# LEDs.net
KiCad netlist of a schematic drawn in Altium Designer
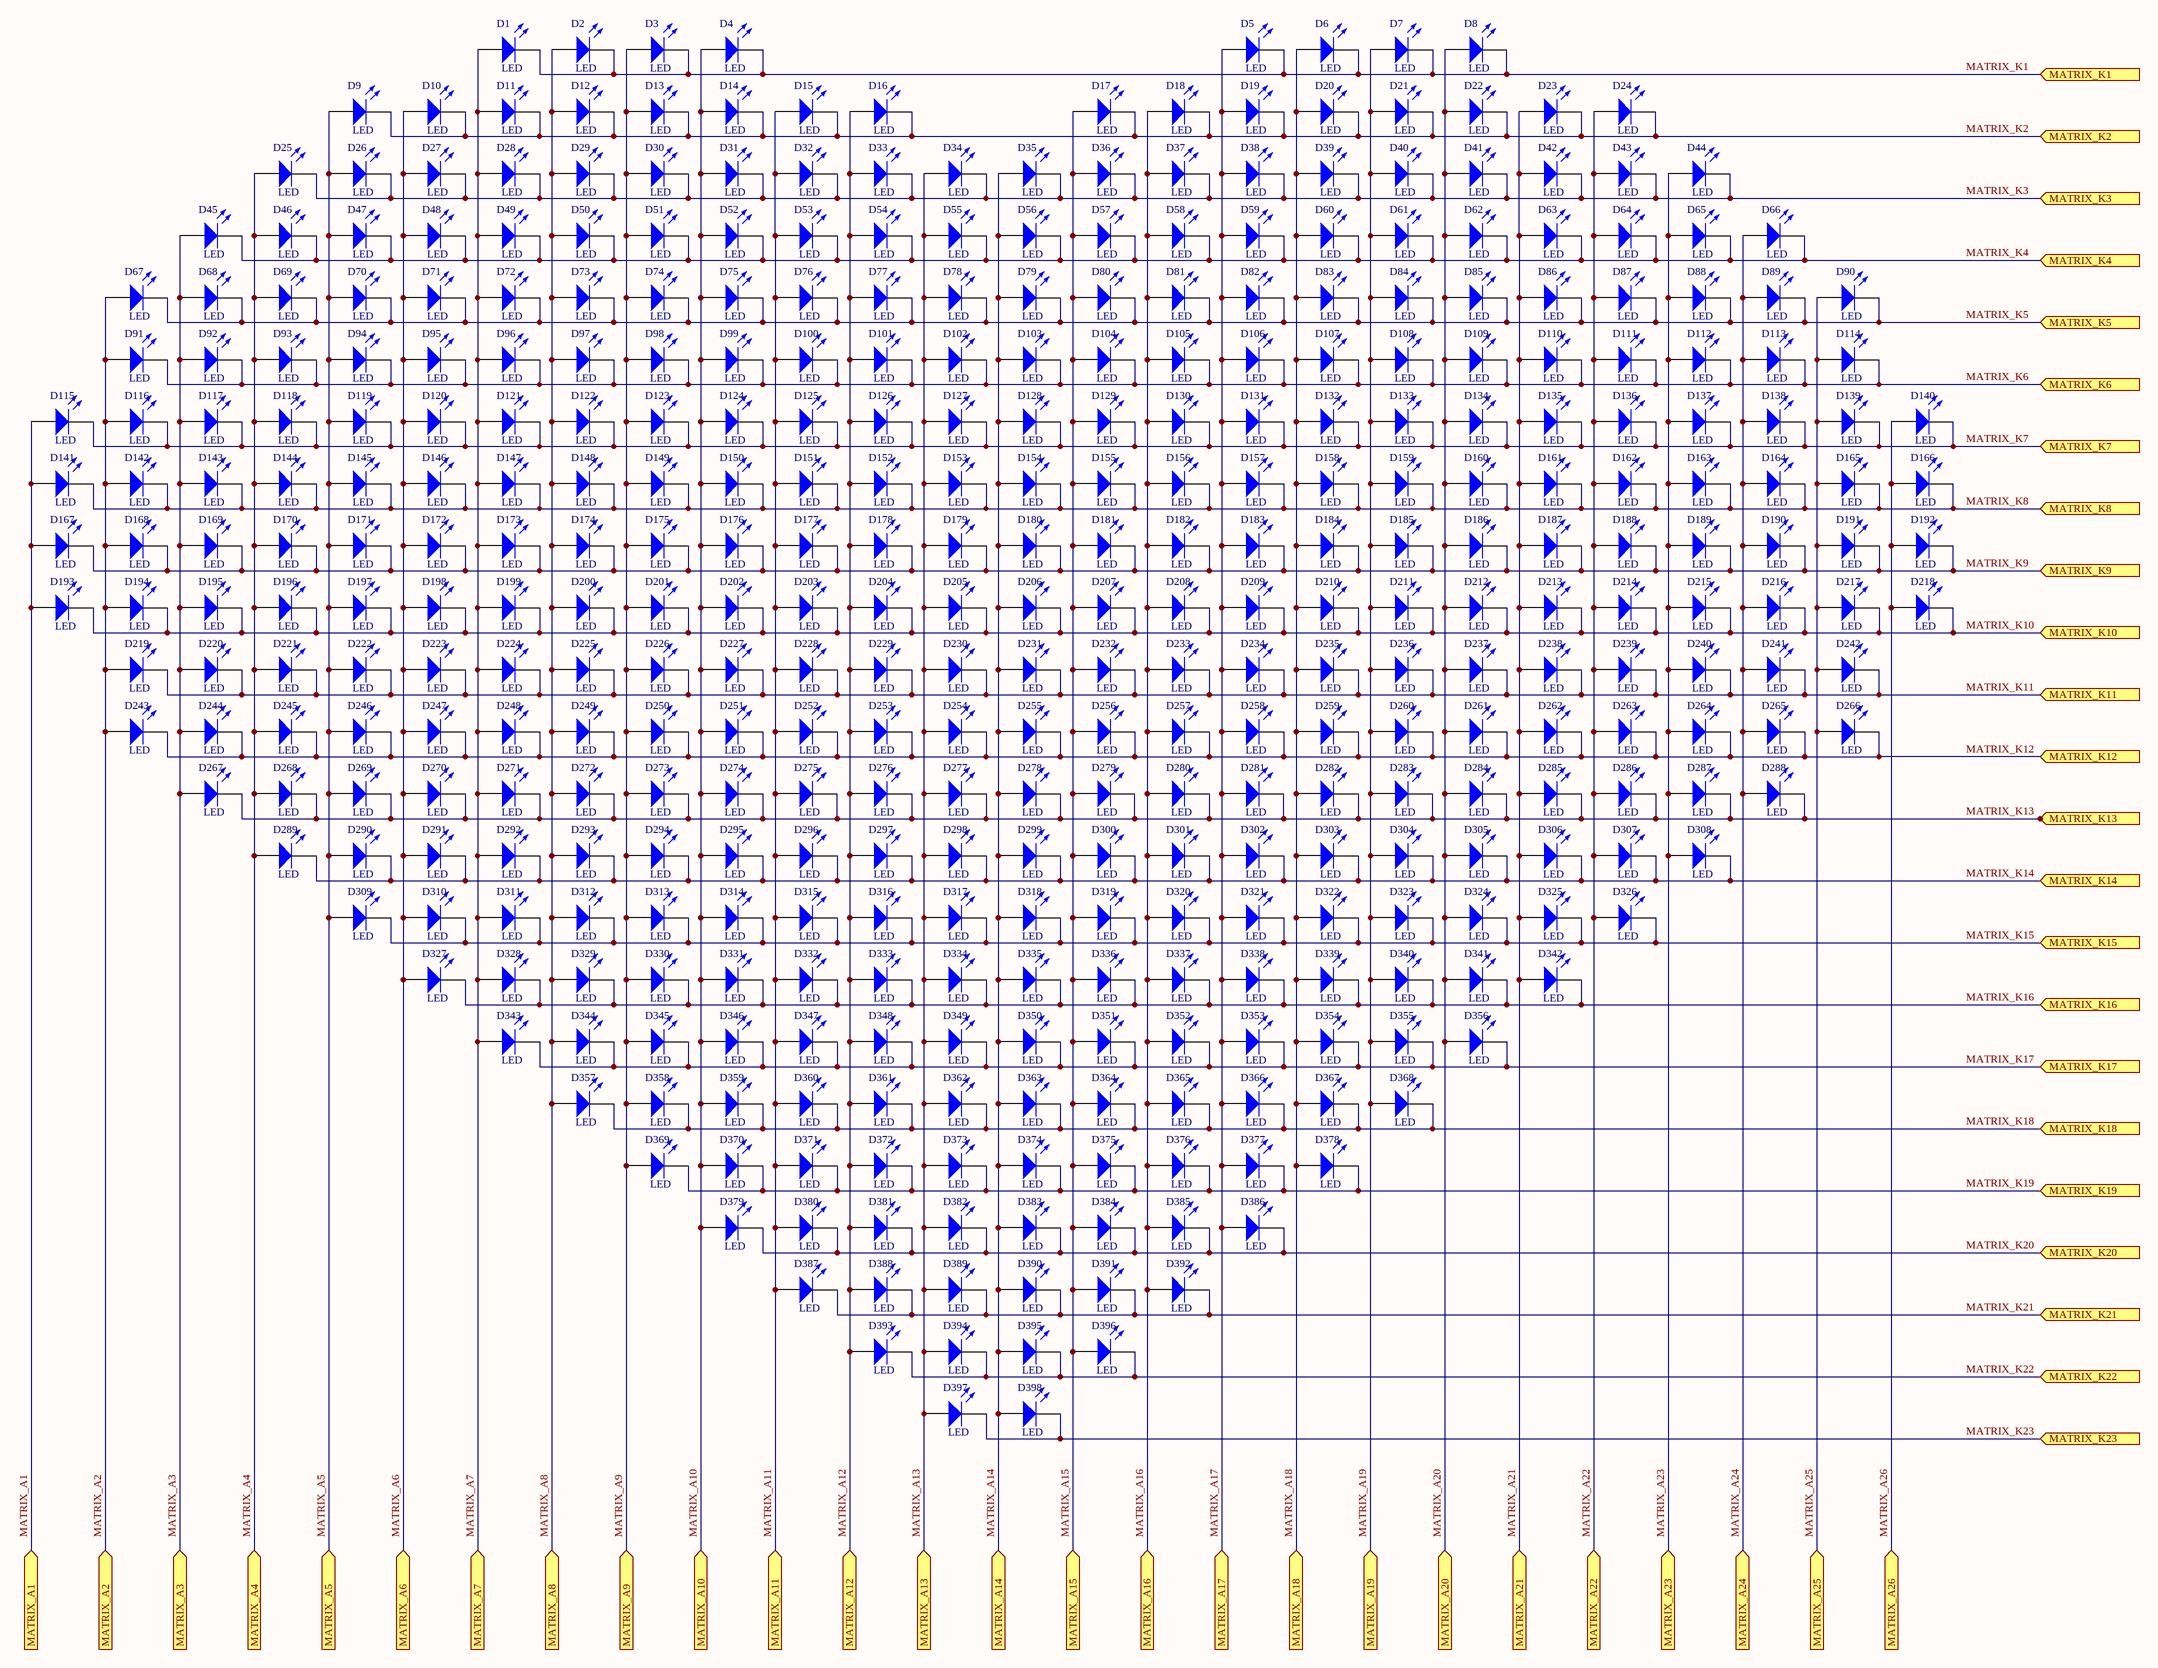
[diagram p0: LEDs.SchDoc]

(export (version "E")
  (design (tool "Eeschema 10.0.6"))
  (components
    (comp (ref "D1")
      (value "LED")
      (footprint "led_3mm")
      (description "Typical INFRARED GaAs LED")
      (fields (field (name "PUBLISHER") "Altium Limited"))
      (libsource (lib "Lib_Sch") (part "LED"))
    )
    (comp (ref "D2")
      (value "LED")
      (footprint "led_3mm")
      (description "Typical INFRARED GaAs LED")
      (fields (field (name "PUBLISHER") "Altium Limited"))
      (libsource (lib "Lib_Sch") (part "LED"))
    )
    (comp (ref "D3")
      (value "LED")
      (footprint "led_3mm")
      (description "Typical INFRARED GaAs LED")
      (fields (field (name "PUBLISHER") "Altium Limited"))
      (libsource (lib "Lib_Sch") (part "LED"))
    )
    (comp (ref "D4")
      (value "LED")
      (footprint "led_3mm")
      (description "Typical INFRARED GaAs LED")
      (fields (field (name "PUBLISHER") "Altium Limited"))
      (libsource (lib "Lib_Sch") (part "LED"))
    )
    (comp (ref "D5")
      (value "LED")
      (footprint "led_3mm")
      (description "Typical INFRARED GaAs LED")
      (fields (field (name "PUBLISHER") "Altium Limited"))
      (libsource (lib "Lib_Sch") (part "LED"))
    )
    (comp (ref "D6")
      (value "LED")
      (footprint "led_3mm")
      (description "Typical INFRARED GaAs LED")
      (fields (field (name "PUBLISHER") "Altium Limited"))
      (libsource (lib "Lib_Sch") (part "LED"))
    )
    (comp (ref "D7")
      (value "LED")
      (footprint "led_3mm")
      (description "Typical INFRARED GaAs LED")
      (fields (field (name "PUBLISHER") "Altium Limited"))
      (libsource (lib "Lib_Sch") (part "LED"))
    )
    (comp (ref "D8")
      (value "LED")
      (footprint "led_3mm")
      (description "Typical INFRARED GaAs LED")
      (fields (field (name "PUBLISHER") "Altium Limited"))
      (libsource (lib "Lib_Sch") (part "LED"))
    )
    (comp (ref "D9")
      (value "LED")
      (footprint "led_3mm")
      (description "Typical INFRARED GaAs LED")
      (fields (field (name "PUBLISHER") "Altium Limited"))
      (libsource (lib "Lib_Sch") (part "LED"))
    )
    (comp (ref "D10")
      (value "LED")
      (footprint "led_3mm")
      (description "Typical INFRARED GaAs LED")
      (fields (field (name "PUBLISHER") "Altium Limited"))
      (libsource (lib "Lib_Sch") (part "LED"))
    )
    (comp (ref "D11")
      (value "LED")
      (footprint "led_3mm")
      (description "Typical INFRARED GaAs LED")
      (fields (field (name "PUBLISHER") "Altium Limited"))
      (libsource (lib "Lib_Sch") (part "LED"))
    )
    (comp (ref "D12")
      (value "LED")
      (footprint "led_3mm")
      (description "Typical INFRARED GaAs LED")
      (fields (field (name "PUBLISHER") "Altium Limited"))
      (libsource (lib "Lib_Sch") (part "LED"))
    )
    (comp (ref "D13")
      (value "LED")
      (footprint "led_3mm")
      (description "Typical INFRARED GaAs LED")
      (fields (field (name "PUBLISHER") "Altium Limited"))
      (libsource (lib "Lib_Sch") (part "LED"))
    )
    (comp (ref "D14")
      (value "LED")
      (footprint "led_3mm")
      (description "Typical INFRARED GaAs LED")
      (fields (field (name "PUBLISHER") "Altium Limited"))
      (libsource (lib "Lib_Sch") (part "LED"))
    )
    (comp (ref "D15")
      (value "LED")
      (footprint "led_3mm")
      (description "Typical INFRARED GaAs LED")
      (fields (field (name "PUBLISHER") "Altium Limited"))
      (libsource (lib "Lib_Sch") (part "LED"))
    )
    (comp (ref "D16")
      (value "LED")
      (footprint "led_3mm")
      (description "Typical INFRARED GaAs LED")
      (fields (field (name "PUBLISHER") "Altium Limited"))
      (libsource (lib "Lib_Sch") (part "LED"))
    )
    (comp (ref "D17")
      (value "LED")
      (footprint "led_3mm")
      (description "Typical INFRARED GaAs LED")
      (fields (field (name "PUBLISHER") "Altium Limited"))
      (libsource (lib "Lib_Sch") (part "LED"))
    )
    (comp (ref "D18")
      (value "LED")
      (footprint "led_3mm")
      (description "Typical INFRARED GaAs LED")
      (fields (field (name "PUBLISHER") "Altium Limited"))
      (libsource (lib "Lib_Sch") (part "LED"))
    )
    (comp (ref "D19")
      (value "LED")
      (footprint "led_3mm")
      (description "Typical INFRARED GaAs LED")
      (fields (field (name "PUBLISHER") "Altium Limited"))
      (libsource (lib "Lib_Sch") (part "LED"))
    )
    (comp (ref "D20")
      (value "LED")
      (footprint "led_3mm")
      (description "Typical INFRARED GaAs LED")
      (fields (field (name "PUBLISHER") "Altium Limited"))
      (libsource (lib "Lib_Sch") (part "LED"))
    )
    (comp (ref "D21")
      (value "LED")
      (footprint "led_3mm")
      (description "Typical INFRARED GaAs LED")
      (fields (field (name "PUBLISHER") "Altium Limited"))
      (libsource (lib "Lib_Sch") (part "LED"))
    )
    (comp (ref "D22")
      (value "LED")
      (footprint "led_3mm")
      (description "Typical INFRARED GaAs LED")
      (fields (field (name "PUBLISHER") "Altium Limited"))
      (libsource (lib "Lib_Sch") (part "LED"))
    )
    (comp (ref "D23")
      (value "LED")
      (footprint "led_3mm")
      (description "Typical INFRARED GaAs LED")
      (fields (field (name "PUBLISHER") "Altium Limited"))
      (libsource (lib "Lib_Sch") (part "LED"))
    )
    (comp (ref "D24")
      (value "LED")
      (footprint "led_3mm")
      (description "Typical INFRARED GaAs LED")
      (fields (field (name "PUBLISHER") "Altium Limited"))
      (libsource (lib "Lib_Sch") (part "LED"))
    )
    (comp (ref "D25")
      (value "LED")
      (footprint "led_3mm")
      (description "Typical INFRARED GaAs LED")
      (fields (field (name "PUBLISHER") "Altium Limited"))
      (libsource (lib "Lib_Sch") (part "LED"))
    )
    (comp (ref "D26")
      (value "LED")
      (footprint "led_3mm")
      (description "Typical INFRARED GaAs LED")
      (fields (field (name "PUBLISHER") "Altium Limited"))
      (libsource (lib "Lib_Sch") (part "LED"))
    )
    (comp (ref "D27")
      (value "LED")
      (footprint "led_3mm")
      (description "Typical INFRARED GaAs LED")
      (fields (field (name "PUBLISHER") "Altium Limited"))
      (libsource (lib "Lib_Sch") (part "LED"))
    )
    (comp (ref "D28")
      (value "LED")
      (footprint "led_3mm")
      (description "Typical INFRARED GaAs LED")
      (fields (field (name "PUBLISHER") "Altium Limited"))
      (libsource (lib "Lib_Sch") (part "LED"))
    )
    (comp (ref "D29")
      (value "LED")
      (footprint "led_3mm")
      (description "Typical INFRARED GaAs LED")
      (fields (field (name "PUBLISHER") "Altium Limited"))
      (libsource (lib "Lib_Sch") (part "LED"))
    )
    (comp (ref "D30")
      (value "LED")
      (footprint "led_3mm")
      (description "Typical INFRARED GaAs LED")
      (fields (field (name "PUBLISHER") "Altium Limited"))
      (libsource (lib "Lib_Sch") (part "LED"))
    )
    (comp (ref "D31")
      (value "LED")
      (footprint "led_3mm")
      (description "Typical INFRARED GaAs LED")
      (fields (field (name "PUBLISHER") "Altium Limited"))
      (libsource (lib "Lib_Sch") (part "LED"))
    )
    (comp (ref "D32")
      (value "LED")
      (footprint "led_3mm")
      (description "Typical INFRARED GaAs LED")
      (fields (field (name "PUBLISHER") "Altium Limited"))
      (libsource (lib "Lib_Sch") (part "LED"))
    )
    (comp (ref "D33")
      (value "LED")
      (footprint "led_3mm")
      (description "Typical INFRARED GaAs LED")
      (fields (field (name "PUBLISHER") "Altium Limited"))
      (libsource (lib "Lib_Sch") (part "LED"))
    )
    (comp (ref "D34")
      (value "LED")
      (footprint "led_3mm")
      (description "Typical INFRARED GaAs LED")
      (fields (field (name "PUBLISHER") "Altium Limited"))
      (libsource (lib "Lib_Sch") (part "LED"))
    )
    (comp (ref "D35")
      (value "LED")
      (footprint "led_3mm")
      (description "Typical INFRARED GaAs LED")
      (fields (field (name "PUBLISHER") "Altium Limited"))
      (libsource (lib "Lib_Sch") (part "LED"))
    )
    (comp (ref "D36")
      (value "LED")
      (footprint "led_3mm")
      (description "Typical INFRARED GaAs LED")
      (fields (field (name "PUBLISHER") "Altium Limited"))
      (libsource (lib "Lib_Sch") (part "LED"))
    )
    (comp (ref "D37")
      (value "LED")
      (footprint "led_3mm")
      (description "Typical INFRARED GaAs LED")
      (fields (field (name "PUBLISHER") "Altium Limited"))
      (libsource (lib "Lib_Sch") (part "LED"))
    )
    (comp (ref "D38")
      (value "LED")
      (footprint "led_3mm")
      (description "Typical INFRARED GaAs LED")
      (fields (field (name "PUBLISHER") "Altium Limited"))
      (libsource (lib "Lib_Sch") (part "LED"))
    )
    (comp (ref "D39")
      (value "LED")
      (footprint "led_3mm")
      (description "Typical INFRARED GaAs LED")
      (fields (field (name "PUBLISHER") "Altium Limited"))
      (libsource (lib "Lib_Sch") (part "LED"))
    )
    (comp (ref "D40")
      (value "LED")
      (footprint "led_3mm")
      (description "Typical INFRARED GaAs LED")
      (fields (field (name "PUBLISHER") "Altium Limited"))
      (libsource (lib "Lib_Sch") (part "LED"))
    )
    (comp (ref "D41")
      (value "LED")
      (footprint "led_3mm")
      (description "Typical INFRARED GaAs LED")
      (fields (field (name "PUBLISHER") "Altium Limited"))
      (libsource (lib "Lib_Sch") (part "LED"))
    )
    (comp (ref "D42")
      (value "LED")
      (footprint "led_3mm")
      (description "Typical INFRARED GaAs LED")
      (fields (field (name "PUBLISHER") "Altium Limited"))
      (libsource (lib "Lib_Sch") (part "LED"))
    )
    (comp (ref "D43")
      (value "LED")
      (footprint "led_3mm")
      (description "Typical INFRARED GaAs LED")
      (fields (field (name "PUBLISHER") "Altium Limited"))
      (libsource (lib "Lib_Sch") (part "LED"))
    )
    (comp (ref "D44")
      (value "LED")
      (footprint "led_3mm")
      (description "Typical INFRARED GaAs LED")
      (fields (field (name "PUBLISHER") "Altium Limited"))
      (libsource (lib "Lib_Sch") (part "LED"))
    )
    (comp (ref "D45")
      (value "LED")
      (footprint "led_3mm")
      (description "Typical INFRARED GaAs LED")
      (fields (field (name "PUBLISHER") "Altium Limited"))
      (libsource (lib "Lib_Sch") (part "LED"))
    )
    (comp (ref "D46")
      (value "LED")
      (footprint "led_3mm")
      (description "Typical INFRARED GaAs LED")
      (fields (field (name "PUBLISHER") "Altium Limited"))
      (libsource (lib "Lib_Sch") (part "LED"))
    )
    (comp (ref "D47")
      (value "LED")
      (footprint "led_3mm")
      (description "Typical INFRARED GaAs LED")
      (fields (field (name "PUBLISHER") "Altium Limited"))
      (libsource (lib "Lib_Sch") (part "LED"))
    )
    (comp (ref "D48")
      (value "LED")
      (footprint "led_3mm")
      (description "Typical INFRARED GaAs LED")
      (fields (field (name "PUBLISHER") "Altium Limited"))
      (libsource (lib "Lib_Sch") (part "LED"))
    )
    (comp (ref "D49")
      (value "LED")
      (footprint "led_3mm")
      (description "Typical INFRARED GaAs LED")
      (fields (field (name "PUBLISHER") "Altium Limited"))
      (libsource (lib "Lib_Sch") (part "LED"))
    )
    (comp (ref "D50")
      (value "LED")
      (footprint "led_3mm")
      (description "Typical INFRARED GaAs LED")
      (fields (field (name "PUBLISHER") "Altium Limited"))
      (libsource (lib "Lib_Sch") (part "LED"))
    )
    (comp (ref "D51")
      (value "LED")
      (footprint "led_3mm")
      (description "Typical INFRARED GaAs LED")
      (fields (field (name "PUBLISHER") "Altium Limited"))
      (libsource (lib "Lib_Sch") (part "LED"))
    )
    (comp (ref "D52")
      (value "LED")
      (footprint "led_3mm")
      (description "Typical INFRARED GaAs LED")
      (fields (field (name "PUBLISHER") "Altium Limited"))
      (libsource (lib "Lib_Sch") (part "LED"))
    )
    (comp (ref "D53")
      (value "LED")
      (footprint "led_3mm")
      (description "Typical INFRARED GaAs LED")
      (fields (field (name "PUBLISHER") "Altium Limited"))
      (libsource (lib "Lib_Sch") (part "LED"))
    )
    (comp (ref "D54")
      (value "LED")
      (footprint "led_3mm")
      (description "Typical INFRARED GaAs LED")
      (fields (field (name "PUBLISHER") "Altium Limited"))
      (libsource (lib "Lib_Sch") (part "LED"))
    )
    (comp (ref "D55")
      (value "LED")
      (footprint "led_3mm")
      (description "Typical INFRARED GaAs LED")
      (fields (field (name "PUBLISHER") "Altium Limited"))
      (libsource (lib "Lib_Sch") (part "LED"))
    )
    (comp (ref "D56")
      (value "LED")
      (footprint "led_3mm")
      (description "Typical INFRARED GaAs LED")
      (fields (field (name "PUBLISHER") "Altium Limited"))
      (libsource (lib "Lib_Sch") (part "LED"))
    )
    (comp (ref "D57")
      (value "LED")
      (footprint "led_3mm")
      (description "Typical INFRARED GaAs LED")
      (fields (field (name "PUBLISHER") "Altium Limited"))
      (libsource (lib "Lib_Sch") (part "LED"))
    )
    (comp (ref "D58")
      (value "LED")
      (footprint "led_3mm")
      (description "Typical INFRARED GaAs LED")
      (fields (field (name "PUBLISHER") "Altium Limited"))
      (libsource (lib "Lib_Sch") (part "LED"))
    )
    (comp (ref "D59")
      (value "LED")
      (footprint "led_3mm")
      (description "Typical INFRARED GaAs LED")
      (fields (field (name "PUBLISHER") "Altium Limited"))
      (libsource (lib "Lib_Sch") (part "LED"))
    )
    (comp (ref "D60")
      (value "LED")
      (footprint "led_3mm")
      (description "Typical INFRARED GaAs LED")
      (fields (field (name "PUBLISHER") "Altium Limited"))
      (libsource (lib "Lib_Sch") (part "LED"))
    )
    (comp (ref "D61")
      (value "LED")
      (footprint "led_3mm")
      (description "Typical INFRARED GaAs LED")
      (fields (field (name "PUBLISHER") "Altium Limited"))
      (libsource (lib "Lib_Sch") (part "LED"))
    )
    (comp (ref "D62")
      (value "LED")
      (footprint "led_3mm")
      (description "Typical INFRARED GaAs LED")
      (fields (field (name "PUBLISHER") "Altium Limited"))
      (libsource (lib "Lib_Sch") (part "LED"))
    )
    (comp (ref "D63")
      (value "LED")
      (footprint "led_3mm")
      (description "Typical INFRARED GaAs LED")
      (fields (field (name "PUBLISHER") "Altium Limited"))
      (libsource (lib "Lib_Sch") (part "LED"))
    )
    (comp (ref "D64")
      (value "LED")
      (footprint "led_3mm")
      (description "Typical INFRARED GaAs LED")
      (fields (field (name "PUBLISHER") "Altium Limited"))
      (libsource (lib "Lib_Sch") (part "LED"))
    )
    (comp (ref "D65")
      (value "LED")
      (footprint "led_3mm")
      (description "Typical INFRARED GaAs LED")
      (fields (field (name "PUBLISHER") "Altium Limited"))
      (libsource (lib "Lib_Sch") (part "LED"))
    )
    (comp (ref "D66")
      (value "LED")
      (footprint "led_3mm")
      (description "Typical INFRARED GaAs LED")
      (fields (field (name "PUBLISHER") "Altium Limited"))
      (libsource (lib "Lib_Sch") (part "LED"))
    )
    (comp (ref "D67")
      (value "LED")
      (footprint "led_3mm")
      (description "Typical INFRARED GaAs LED")
      (fields (field (name "PUBLISHER") "Altium Limited"))
      (libsource (lib "Lib_Sch") (part "LED"))
    )
    (comp (ref "D68")
      (value "LED")
      (footprint "led_3mm")
      (description "Typical INFRARED GaAs LED")
      (fields (field (name "PUBLISHER") "Altium Limited"))
      (libsource (lib "Lib_Sch") (part "LED"))
    )
    (comp (ref "D69")
      (value "LED")
      (footprint "led_3mm")
      (description "Typical INFRARED GaAs LED")
      (fields (field (name "PUBLISHER") "Altium Limited"))
      (libsource (lib "Lib_Sch") (part "LED"))
    )
    (comp (ref "D70")
      (value "LED")
      (footprint "led_3mm")
      (description "Typical INFRARED GaAs LED")
      (fields (field (name "PUBLISHER") "Altium Limited"))
      (libsource (lib "Lib_Sch") (part "LED"))
    )
    (comp (ref "D71")
      (value "LED")
      (footprint "led_3mm")
      (description "Typical INFRARED GaAs LED")
      (fields (field (name "PUBLISHER") "Altium Limited"))
      (libsource (lib "Lib_Sch") (part "LED"))
    )
    (comp (ref "D72")
      (value "LED")
      (footprint "led_3mm")
      (description "Typical INFRARED GaAs LED")
      (fields (field (name "PUBLISHER") "Altium Limited"))
      (libsource (lib "Lib_Sch") (part "LED"))
    )
    (comp (ref "D73")
      (value "LED")
      (footprint "led_3mm")
      (description "Typical INFRARED GaAs LED")
      (fields (field (name "PUBLISHER") "Altium Limited"))
      (libsource (lib "Lib_Sch") (part "LED"))
    )
    (comp (ref "D74")
      (value "LED")
      (footprint "led_3mm")
      (description "Typical INFRARED GaAs LED")
      (fields (field (name "PUBLISHER") "Altium Limited"))
      (libsource (lib "Lib_Sch") (part "LED"))
    )
    (comp (ref "D75")
      (value "LED")
      (footprint "led_3mm")
      (description "Typical INFRARED GaAs LED")
      (fields (field (name "PUBLISHER") "Altium Limited"))
      (libsource (lib "Lib_Sch") (part "LED"))
    )
    (comp (ref "D76")
      (value "LED")
      (footprint "led_3mm")
      (description "Typical INFRARED GaAs LED")
      (fields (field (name "PUBLISHER") "Altium Limited"))
      (libsource (lib "Lib_Sch") (part "LED"))
    )
    (comp (ref "D77")
      (value "LED")
      (footprint "led_3mm")
      (description "Typical INFRARED GaAs LED")
      (fields (field (name "PUBLISHER") "Altium Limited"))
      (libsource (lib "Lib_Sch") (part "LED"))
    )
    (comp (ref "D78")
      (value "LED")
      (footprint "led_3mm")
      (description "Typical INFRARED GaAs LED")
      (fields (field (name "PUBLISHER") "Altium Limited"))
      (libsource (lib "Lib_Sch") (part "LED"))
    )
    (comp (ref "D79")
      (value "LED")
      (footprint "led_3mm")
      (description "Typical INFRARED GaAs LED")
      (fields (field (name "PUBLISHER") "Altium Limited"))
      (libsource (lib "Lib_Sch") (part "LED"))
    )
    (comp (ref "D80")
      (value "LED")
      (footprint "led_3mm")
      (description "Typical INFRARED GaAs LED")
      (fields (field (name "PUBLISHER") "Altium Limited"))
      (libsource (lib "Lib_Sch") (part "LED"))
    )
    (comp (ref "D81")
      (value "LED")
      (footprint "led_3mm")
      (description "Typical INFRARED GaAs LED")
      (fields (field (name "PUBLISHER") "Altium Limited"))
      (libsource (lib "Lib_Sch") (part "LED"))
    )
    (comp (ref "D82")
      (value "LED")
      (footprint "led_3mm")
      (description "Typical INFRARED GaAs LED")
      (fields (field (name "PUBLISHER") "Altium Limited"))
      (libsource (lib "Lib_Sch") (part "LED"))
    )
    (comp (ref "D83")
      (value "LED")
      (footprint "led_3mm")
      (description "Typical INFRARED GaAs LED")
      (fields (field (name "PUBLISHER") "Altium Limited"))
      (libsource (lib "Lib_Sch") (part "LED"))
    )
    (comp (ref "D84")
      (value "LED")
      (footprint "led_3mm")
      (description "Typical INFRARED GaAs LED")
      (fields (field (name "PUBLISHER") "Altium Limited"))
      (libsource (lib "Lib_Sch") (part "LED"))
    )
    (comp (ref "D85")
      (value "LED")
      (footprint "led_3mm")
      (description "Typical INFRARED GaAs LED")
      (fields (field (name "PUBLISHER") "Altium Limited"))
      (libsource (lib "Lib_Sch") (part "LED"))
    )
    (comp (ref "D86")
      (value "LED")
      (footprint "led_3mm")
      (description "Typical INFRARED GaAs LED")
      (fields (field (name "PUBLISHER") "Altium Limited"))
      (libsource (lib "Lib_Sch") (part "LED"))
    )
    (comp (ref "D87")
      (value "LED")
      (footprint "led_3mm")
      (description "Typical INFRARED GaAs LED")
      (fields (field (name "PUBLISHER") "Altium Limited"))
      (libsource (lib "Lib_Sch") (part "LED"))
    )
    (comp (ref "D88")
      (value "LED")
      (footprint "led_3mm")
      (description "Typical INFRARED GaAs LED")
      (fields (field (name "PUBLISHER") "Altium Limited"))
      (libsource (lib "Lib_Sch") (part "LED"))
    )
    (comp (ref "D89")
      (value "LED")
      (footprint "led_3mm")
      (description "Typical INFRARED GaAs LED")
      (fields (field (name "PUBLISHER") "Altium Limited"))
      (libsource (lib "Lib_Sch") (part "LED"))
    )
    (comp (ref "D90")
      (value "LED")
      (footprint "led_3mm")
      (description "Typical INFRARED GaAs LED")
      (fields (field (name "PUBLISHER") "Altium Limited"))
      (libsource (lib "Lib_Sch") (part "LED"))
    )
    (comp (ref "D91")
      (value "LED")
      (footprint "led_3mm")
      (description "Typical INFRARED GaAs LED")
      (fields (field (name "PUBLISHER") "Altium Limited"))
      (libsource (lib "Lib_Sch") (part "LED"))
    )
    (comp (ref "D92")
      (value "LED")
      (footprint "led_3mm")
      (description "Typical INFRARED GaAs LED")
      (fields (field (name "PUBLISHER") "Altium Limited"))
      (libsource (lib "Lib_Sch") (part "LED"))
    )
    (comp (ref "D93")
      (value "LED")
      (footprint "led_3mm")
      (description "Typical INFRARED GaAs LED")
      (fields (field (name "PUBLISHER") "Altium Limited"))
      (libsource (lib "Lib_Sch") (part "LED"))
    )
    (comp (ref "D94")
      (value "LED")
      (footprint "led_3mm")
      (description "Typical INFRARED GaAs LED")
      (fields (field (name "PUBLISHER") "Altium Limited"))
      (libsource (lib "Lib_Sch") (part "LED"))
    )
    (comp (ref "D95")
      (value "LED")
      (footprint "led_3mm")
      (description "Typical INFRARED GaAs LED")
      (fields (field (name "PUBLISHER") "Altium Limited"))
      (libsource (lib "Lib_Sch") (part "LED"))
    )
    (comp (ref "D96")
      (value "LED")
      (footprint "led_3mm")
      (description "Typical INFRARED GaAs LED")
      (fields (field (name "PUBLISHER") "Altium Limited"))
      (libsource (lib "Lib_Sch") (part "LED"))
    )
    (comp (ref "D97")
      (value "LED")
      (footprint "led_3mm")
      (description "Typical INFRARED GaAs LED")
      (fields (field (name "PUBLISHER") "Altium Limited"))
      (libsource (lib "Lib_Sch") (part "LED"))
    )
    (comp (ref "D98")
      (value "LED")
      (footprint "led_3mm")
      (description "Typical INFRARED GaAs LED")
      (fields (field (name "PUBLISHER") "Altium Limited"))
      (libsource (lib "Lib_Sch") (part "LED"))
    )
    (comp (ref "D99")
      (value "LED")
      (footprint "led_3mm")
      (description "Typical INFRARED GaAs LED")
      (fields (field (name "PUBLISHER") "Altium Limited"))
      (libsource (lib "Lib_Sch") (part "LED"))
    )
    (comp (ref "D100")
      (value "LED")
      (footprint "led_3mm")
      (description "Typical INFRARED GaAs LED")
      (fields (field (name "PUBLISHER") "Altium Limited"))
      (libsource (lib "Lib_Sch") (part "LED"))
    )
    (comp (ref "D101")
      (value "LED")
      (footprint "led_3mm")
      (description "Typical INFRARED GaAs LED")
      (fields (field (name "PUBLISHER") "Altium Limited"))
      (libsource (lib "Lib_Sch") (part "LED"))
    )
    (comp (ref "D102")
      (value "LED")
      (footprint "led_3mm")
      (description "Typical INFRARED GaAs LED")
      (fields (field (name "PUBLISHER") "Altium Limited"))
      (libsource (lib "Lib_Sch") (part "LED"))
    )
    (comp (ref "D103")
      (value "LED")
      (footprint "led_3mm")
      (description "Typical INFRARED GaAs LED")
      (fields (field (name "PUBLISHER") "Altium Limited"))
      (libsource (lib "Lib_Sch") (part "LED"))
    )
    (comp (ref "D104")
      (value "LED")
      (footprint "led_3mm")
      (description "Typical INFRARED GaAs LED")
      (fields (field (name "PUBLISHER") "Altium Limited"))
      (libsource (lib "Lib_Sch") (part "LED"))
    )
    (comp (ref "D105")
      (value "LED")
      (footprint "led_3mm")
      (description "Typical INFRARED GaAs LED")
      (fields (field (name "PUBLISHER") "Altium Limited"))
      (libsource (lib "Lib_Sch") (part "LED"))
    )
    (comp (ref "D106")
      (value "LED")
      (footprint "led_3mm")
      (description "Typical INFRARED GaAs LED")
      (fields (field (name "PUBLISHER") "Altium Limited"))
      (libsource (lib "Lib_Sch") (part "LED"))
    )
    (comp (ref "D107")
      (value "LED")
      (footprint "led_3mm")
      (description "Typical INFRARED GaAs LED")
      (fields (field (name "PUBLISHER") "Altium Limited"))
      (libsource (lib "Lib_Sch") (part "LED"))
    )
    (comp (ref "D108")
      (value "LED")
      (footprint "led_3mm")
      (description "Typical INFRARED GaAs LED")
      (fields (field (name "PUBLISHER") "Altium Limited"))
      (libsource (lib "Lib_Sch") (part "LED"))
    )
    (comp (ref "D109")
      (value "LED")
      (footprint "led_3mm")
      (description "Typical INFRARED GaAs LED")
      (fields (field (name "PUBLISHER") "Altium Limited"))
      (libsource (lib "Lib_Sch") (part "LED"))
    )
    (comp (ref "D110")
      (value "LED")
      (footprint "led_3mm")
      (description "Typical INFRARED GaAs LED")
      (fields (field (name "PUBLISHER") "Altium Limited"))
      (libsource (lib "Lib_Sch") (part "LED"))
    )
    (comp (ref "D111")
      (value "LED")
      (footprint "led_3mm")
      (description "Typical INFRARED GaAs LED")
      (fields (field (name "PUBLISHER") "Altium Limited"))
      (libsource (lib "Lib_Sch") (part "LED"))
    )
    (comp (ref "D112")
      (value "LED")
      (footprint "led_3mm")
      (description "Typical INFRARED GaAs LED")
      (fields (field (name "PUBLISHER") "Altium Limited"))
      (libsource (lib "Lib_Sch") (part "LED"))
    )
    (comp (ref "D113")
      (value "LED")
      (footprint "led_3mm")
      (description "Typical INFRARED GaAs LED")
      (fields (field (name "PUBLISHER") "Altium Limited"))
      (libsource (lib "Lib_Sch") (part "LED"))
    )
    (comp (ref "D114")
      (value "LED")
      (footprint "led_3mm")
      (description "Typical INFRARED GaAs LED")
      (fields (field (name "PUBLISHER") "Altium Limited"))
      (libsource (lib "Lib_Sch") (part "LED"))
    )
    (comp (ref "D115")
      (value "LED")
      (footprint "led_3mm")
      (description "Typical INFRARED GaAs LED")
      (fields (field (name "PUBLISHER") "Altium Limited"))
      (libsource (lib "Lib_Sch") (part "LED"))
    )
    (comp (ref "D116")
      (value "LED")
      (footprint "led_3mm")
      (description "Typical INFRARED GaAs LED")
      (fields (field (name "PUBLISHER") "Altium Limited"))
      (libsource (lib "Lib_Sch") (part "LED"))
    )
    (comp (ref "D117")
      (value "LED")
      (footprint "led_3mm")
      (description "Typical INFRARED GaAs LED")
      (fields (field (name "PUBLISHER") "Altium Limited"))
      (libsource (lib "Lib_Sch") (part "LED"))
    )
    (comp (ref "D118")
      (value "LED")
      (footprint "led_3mm")
      (description "Typical INFRARED GaAs LED")
      (fields (field (name "PUBLISHER") "Altium Limited"))
      (libsource (lib "Lib_Sch") (part "LED"))
    )
    (comp (ref "D119")
      (value "LED")
      (footprint "led_3mm")
      (description "Typical INFRARED GaAs LED")
      (fields (field (name "PUBLISHER") "Altium Limited"))
      (libsource (lib "Lib_Sch") (part "LED"))
    )
    (comp (ref "D120")
      (value "LED")
      (footprint "led_3mm")
      (description "Typical INFRARED GaAs LED")
      (fields (field (name "PUBLISHER") "Altium Limited"))
      (libsource (lib "Lib_Sch") (part "LED"))
    )
    (comp (ref "D121")
      (value "LED")
      (footprint "led_3mm")
      (description "Typical INFRARED GaAs LED")
      (fields (field (name "PUBLISHER") "Altium Limited"))
      (libsource (lib "Lib_Sch") (part "LED"))
    )
    (comp (ref "D122")
      (value "LED")
      (footprint "led_3mm")
      (description "Typical INFRARED GaAs LED")
      (fields (field (name "PUBLISHER") "Altium Limited"))
      (libsource (lib "Lib_Sch") (part "LED"))
    )
    (comp (ref "D123")
      (value "LED")
      (footprint "led_3mm")
      (description "Typical INFRARED GaAs LED")
      (fields (field (name "PUBLISHER") "Altium Limited"))
      (libsource (lib "Lib_Sch") (part "LED"))
    )
    (comp (ref "D124")
      (value "LED")
      (footprint "led_3mm")
      (description "Typical INFRARED GaAs LED")
      (fields (field (name "PUBLISHER") "Altium Limited"))
      (libsource (lib "Lib_Sch") (part "LED"))
    )
    (comp (ref "D125")
      (value "LED")
      (footprint "led_3mm")
      (description "Typical INFRARED GaAs LED")
      (fields (field (name "PUBLISHER") "Altium Limited"))
      (libsource (lib "Lib_Sch") (part "LED"))
    )
    (comp (ref "D126")
      (value "LED")
      (footprint "led_3mm")
      (description "Typical INFRARED GaAs LED")
      (fields (field (name "PUBLISHER") "Altium Limited"))
      (libsource (lib "Lib_Sch") (part "LED"))
    )
    (comp (ref "D127")
      (value "LED")
      (footprint "led_3mm")
      (description "Typical INFRARED GaAs LED")
      (fields (field (name "PUBLISHER") "Altium Limited"))
      (libsource (lib "Lib_Sch") (part "LED"))
    )
    (comp (ref "D128")
      (value "LED")
      (footprint "led_3mm")
      (description "Typical INFRARED GaAs LED")
      (fields (field (name "PUBLISHER") "Altium Limited"))
      (libsource (lib "Lib_Sch") (part "LED"))
    )
    (comp (ref "D129")
      (value "LED")
      (footprint "led_3mm")
      (description "Typical INFRARED GaAs LED")
      (fields (field (name "PUBLISHER") "Altium Limited"))
      (libsource (lib "Lib_Sch") (part "LED"))
    )
    (comp (ref "D130")
      (value "LED")
      (footprint "led_3mm")
      (description "Typical INFRARED GaAs LED")
      (fields (field (name "PUBLISHER") "Altium Limited"))
      (libsource (lib "Lib_Sch") (part "LED"))
    )
    (comp (ref "D131")
      (value "LED")
      (footprint "led_3mm")
      (description "Typical INFRARED GaAs LED")
      (fields (field (name "PUBLISHER") "Altium Limited"))
      (libsource (lib "Lib_Sch") (part "LED"))
    )
    (comp (ref "D132")
      (value "LED")
      (footprint "led_3mm")
      (description "Typical INFRARED GaAs LED")
      (fields (field (name "PUBLISHER") "Altium Limited"))
      (libsource (lib "Lib_Sch") (part "LED"))
    )
    (comp (ref "D133")
      (value "LED")
      (footprint "led_3mm")
      (description "Typical INFRARED GaAs LED")
      (fields (field (name "PUBLISHER") "Altium Limited"))
      (libsource (lib "Lib_Sch") (part "LED"))
    )
    (comp (ref "D134")
      (value "LED")
      (footprint "led_3mm")
      (description "Typical INFRARED GaAs LED")
      (fields (field (name "PUBLISHER") "Altium Limited"))
      (libsource (lib "Lib_Sch") (part "LED"))
    )
    (comp (ref "D135")
      (value "LED")
      (footprint "led_3mm")
      (description "Typical INFRARED GaAs LED")
      (fields (field (name "PUBLISHER") "Altium Limited"))
      (libsource (lib "Lib_Sch") (part "LED"))
    )
    (comp (ref "D136")
      (value "LED")
      (footprint "led_3mm")
      (description "Typical INFRARED GaAs LED")
      (fields (field (name "PUBLISHER") "Altium Limited"))
      (libsource (lib "Lib_Sch") (part "LED"))
    )
    (comp (ref "D137")
      (value "LED")
      (footprint "led_3mm")
      (description "Typical INFRARED GaAs LED")
      (fields (field (name "PUBLISHER") "Altium Limited"))
      (libsource (lib "Lib_Sch") (part "LED"))
    )
    (comp (ref "D138")
      (value "LED")
      (footprint "led_3mm")
      (description "Typical INFRARED GaAs LED")
      (fields (field (name "PUBLISHER") "Altium Limited"))
      (libsource (lib "Lib_Sch") (part "LED"))
    )
    (comp (ref "D139")
      (value "LED")
      (footprint "led_3mm")
      (description "Typical INFRARED GaAs LED")
      (fields (field (name "PUBLISHER") "Altium Limited"))
      (libsource (lib "Lib_Sch") (part "LED"))
    )
    (comp (ref "D140")
      (value "LED")
      (footprint "led_3mm")
      (description "Typical INFRARED GaAs LED")
      (fields (field (name "PUBLISHER") "Altium Limited"))
      (libsource (lib "Lib_Sch") (part "LED"))
    )
    (comp (ref "D141")
      (value "LED")
      (footprint "led_3mm")
      (description "Typical INFRARED GaAs LED")
      (fields (field (name "PUBLISHER") "Altium Limited"))
      (libsource (lib "Lib_Sch") (part "LED"))
    )
    (comp (ref "D142")
      (value "LED")
      (footprint "led_3mm")
      (description "Typical INFRARED GaAs LED")
      (fields (field (name "PUBLISHER") "Altium Limited"))
      (libsource (lib "Lib_Sch") (part "LED"))
    )
    (comp (ref "D143")
      (value "LED")
      (footprint "led_3mm")
      (description "Typical INFRARED GaAs LED")
      (fields (field (name "PUBLISHER") "Altium Limited"))
      (libsource (lib "Lib_Sch") (part "LED"))
    )
    (comp (ref "D144")
      (value "LED")
      (footprint "led_3mm")
      (description "Typical INFRARED GaAs LED")
      (fields (field (name "PUBLISHER") "Altium Limited"))
      (libsource (lib "Lib_Sch") (part "LED"))
    )
    (comp (ref "D145")
      (value "LED")
      (footprint "led_3mm")
      (description "Typical INFRARED GaAs LED")
      (fields (field (name "PUBLISHER") "Altium Limited"))
      (libsource (lib "Lib_Sch") (part "LED"))
    )
    (comp (ref "D146")
      (value "LED")
      (footprint "led_3mm")
      (description "Typical INFRARED GaAs LED")
      (fields (field (name "PUBLISHER") "Altium Limited"))
      (libsource (lib "Lib_Sch") (part "LED"))
    )
    (comp (ref "D147")
      (value "LED")
      (footprint "led_3mm")
      (description "Typical INFRARED GaAs LED")
      (fields (field (name "PUBLISHER") "Altium Limited"))
      (libsource (lib "Lib_Sch") (part "LED"))
    )
    (comp (ref "D148")
      (value "LED")
      (footprint "led_3mm")
      (description "Typical INFRARED GaAs LED")
      (fields (field (name "PUBLISHER") "Altium Limited"))
      (libsource (lib "Lib_Sch") (part "LED"))
    )
    (comp (ref "D149")
      (value "LED")
      (footprint "led_3mm")
      (description "Typical INFRARED GaAs LED")
      (fields (field (name "PUBLISHER") "Altium Limited"))
      (libsource (lib "Lib_Sch") (part "LED"))
    )
    (comp (ref "D150")
      (value "LED")
      (footprint "led_3mm")
      (description "Typical INFRARED GaAs LED")
      (fields (field (name "PUBLISHER") "Altium Limited"))
      (libsource (lib "Lib_Sch") (part "LED"))
    )
    (comp (ref "D151")
      (value "LED")
      (footprint "led_3mm")
      (description "Typical INFRARED GaAs LED")
      (fields (field (name "PUBLISHER") "Altium Limited"))
      (libsource (lib "Lib_Sch") (part "LED"))
    )
    (comp (ref "D152")
      (value "LED")
      (footprint "led_3mm")
      (description "Typical INFRARED GaAs LED")
      (fields (field (name "PUBLISHER") "Altium Limited"))
      (libsource (lib "Lib_Sch") (part "LED"))
    )
    (comp (ref "D153")
      (value "LED")
      (footprint "led_3mm")
      (description "Typical INFRARED GaAs LED")
      (fields (field (name "PUBLISHER") "Altium Limited"))
      (libsource (lib "Lib_Sch") (part "LED"))
    )
    (comp (ref "D154")
      (value "LED")
      (footprint "led_3mm")
      (description "Typical INFRARED GaAs LED")
      (fields (field (name "PUBLISHER") "Altium Limited"))
      (libsource (lib "Lib_Sch") (part "LED"))
    )
    (comp (ref "D155")
      (value "LED")
      (footprint "led_3mm")
      (description "Typical INFRARED GaAs LED")
      (fields (field (name "PUBLISHER") "Altium Limited"))
      (libsource (lib "Lib_Sch") (part "LED"))
    )
    (comp (ref "D156")
      (value "LED")
      (footprint "led_3mm")
      (description "Typical INFRARED GaAs LED")
      (fields (field (name "PUBLISHER") "Altium Limited"))
      (libsource (lib "Lib_Sch") (part "LED"))
    )
    (comp (ref "D157")
      (value "LED")
      (footprint "led_3mm")
      (description "Typical INFRARED GaAs LED")
      (fields (field (name "PUBLISHER") "Altium Limited"))
      (libsource (lib "Lib_Sch") (part "LED"))
    )
    (comp (ref "D158")
      (value "LED")
      (footprint "led_3mm")
      (description "Typical INFRARED GaAs LED")
      (fields (field (name "PUBLISHER") "Altium Limited"))
      (libsource (lib "Lib_Sch") (part "LED"))
    )
    (comp (ref "D159")
      (value "LED")
      (footprint "led_3mm")
      (description "Typical INFRARED GaAs LED")
      (fields (field (name "PUBLISHER") "Altium Limited"))
      (libsource (lib "Lib_Sch") (part "LED"))
    )
    (comp (ref "D160")
      (value "LED")
      (footprint "led_3mm")
      (description "Typical INFRARED GaAs LED")
      (fields (field (name "PUBLISHER") "Altium Limited"))
      (libsource (lib "Lib_Sch") (part "LED"))
    )
    (comp (ref "D161")
      (value "LED")
      (footprint "led_3mm")
      (description "Typical INFRARED GaAs LED")
      (fields (field (name "PUBLISHER") "Altium Limited"))
      (libsource (lib "Lib_Sch") (part "LED"))
    )
    (comp (ref "D162")
      (value "LED")
      (footprint "led_3mm")
      (description "Typical INFRARED GaAs LED")
      (fields (field (name "PUBLISHER") "Altium Limited"))
      (libsource (lib "Lib_Sch") (part "LED"))
    )
    (comp (ref "D163")
      (value "LED")
      (footprint "led_3mm")
      (description "Typical INFRARED GaAs LED")
      (fields (field (name "PUBLISHER") "Altium Limited"))
      (libsource (lib "Lib_Sch") (part "LED"))
    )
    (comp (ref "D164")
      (value "LED")
      (footprint "led_3mm")
      (description "Typical INFRARED GaAs LED")
      (fields (field (name "PUBLISHER") "Altium Limited"))
      (libsource (lib "Lib_Sch") (part "LED"))
    )
    (comp (ref "D165")
      (value "LED")
      (footprint "led_3mm")
      (description "Typical INFRARED GaAs LED")
      (fields (field (name "PUBLISHER") "Altium Limited"))
      (libsource (lib "Lib_Sch") (part "LED"))
    )
    (comp (ref "D166")
      (value "LED")
      (footprint "led_3mm")
      (description "Typical INFRARED GaAs LED")
      (fields (field (name "PUBLISHER") "Altium Limited"))
      (libsource (lib "Lib_Sch") (part "LED"))
    )
    (comp (ref "D167")
      (value "LED")
      (footprint "led_3mm")
      (description "Typical INFRARED GaAs LED")
      (fields (field (name "PUBLISHER") "Altium Limited"))
      (libsource (lib "Lib_Sch") (part "LED"))
    )
    (comp (ref "D168")
      (value "LED")
      (footprint "led_3mm")
      (description "Typical INFRARED GaAs LED")
      (fields (field (name "PUBLISHER") "Altium Limited"))
      (libsource (lib "Lib_Sch") (part "LED"))
    )
    (comp (ref "D169")
      (value "LED")
      (footprint "led_3mm")
      (description "Typical INFRARED GaAs LED")
      (fields (field (name "PUBLISHER") "Altium Limited"))
      (libsource (lib "Lib_Sch") (part "LED"))
    )
    (comp (ref "D170")
      (value "LED")
      (footprint "led_3mm")
      (description "Typical INFRARED GaAs LED")
      (fields (field (name "PUBLISHER") "Altium Limited"))
      (libsource (lib "Lib_Sch") (part "LED"))
    )
    (comp (ref "D171")
      (value "LED")
      (footprint "led_3mm")
      (description "Typical INFRARED GaAs LED")
      (fields (field (name "PUBLISHER") "Altium Limited"))
      (libsource (lib "Lib_Sch") (part "LED"))
    )
    (comp (ref "D172")
      (value "LED")
      (footprint "led_3mm")
      (description "Typical INFRARED GaAs LED")
      (fields (field (name "PUBLISHER") "Altium Limited"))
      (libsource (lib "Lib_Sch") (part "LED"))
    )
    (comp (ref "D173")
      (value "LED")
      (footprint "led_3mm")
      (description "Typical INFRARED GaAs LED")
      (fields (field (name "PUBLISHER") "Altium Limited"))
      (libsource (lib "Lib_Sch") (part "LED"))
    )
    (comp (ref "D174")
      (value "LED")
      (footprint "led_3mm")
      (description "Typical INFRARED GaAs LED")
      (fields (field (name "PUBLISHER") "Altium Limited"))
      (libsource (lib "Lib_Sch") (part "LED"))
    )
    (comp (ref "D175")
      (value "LED")
      (footprint "led_3mm")
      (description "Typical INFRARED GaAs LED")
      (fields (field (name "PUBLISHER") "Altium Limited"))
      (libsource (lib "Lib_Sch") (part "LED"))
    )
    (comp (ref "D176")
      (value "LED")
      (footprint "led_3mm")
      (description "Typical INFRARED GaAs LED")
      (fields (field (name "PUBLISHER") "Altium Limited"))
      (libsource (lib "Lib_Sch") (part "LED"))
    )
    (comp (ref "D177")
      (value "LED")
      (footprint "led_3mm")
      (description "Typical INFRARED GaAs LED")
      (fields (field (name "PUBLISHER") "Altium Limited"))
      (libsource (lib "Lib_Sch") (part "LED"))
    )
    (comp (ref "D178")
      (value "LED")
      (footprint "led_3mm")
      (description "Typical INFRARED GaAs LED")
      (fields (field (name "PUBLISHER") "Altium Limited"))
      (libsource (lib "Lib_Sch") (part "LED"))
    )
    (comp (ref "D179")
      (value "LED")
      (footprint "led_3mm")
      (description "Typical INFRARED GaAs LED")
      (fields (field (name "PUBLISHER") "Altium Limited"))
      (libsource (lib "Lib_Sch") (part "LED"))
    )
    (comp (ref "D180")
      (value "LED")
      (footprint "led_3mm")
      (description "Typical INFRARED GaAs LED")
      (fields (field (name "PUBLISHER") "Altium Limited"))
      (libsource (lib "Lib_Sch") (part "LED"))
    )
    (comp (ref "D181")
      (value "LED")
      (footprint "led_3mm")
      (description "Typical INFRARED GaAs LED")
      (fields (field (name "PUBLISHER") "Altium Limited"))
      (libsource (lib "Lib_Sch") (part "LED"))
    )
    (comp (ref "D182")
      (value "LED")
      (footprint "led_3mm")
      (description "Typical INFRARED GaAs LED")
      (fields (field (name "PUBLISHER") "Altium Limited"))
      (libsource (lib "Lib_Sch") (part "LED"))
    )
    (comp (ref "D183")
      (value "LED")
      (footprint "led_3mm")
      (description "Typical INFRARED GaAs LED")
      (fields (field (name "PUBLISHER") "Altium Limited"))
      (libsource (lib "Lib_Sch") (part "LED"))
    )
    (comp (ref "D184")
      (value "LED")
      (footprint "led_3mm")
      (description "Typical INFRARED GaAs LED")
      (fields (field (name "PUBLISHER") "Altium Limited"))
      (libsource (lib "Lib_Sch") (part "LED"))
    )
    (comp (ref "D185")
      (value "LED")
      (footprint "led_3mm")
      (description "Typical INFRARED GaAs LED")
      (fields (field (name "PUBLISHER") "Altium Limited"))
      (libsource (lib "Lib_Sch") (part "LED"))
    )
    (comp (ref "D186")
      (value "LED")
      (footprint "led_3mm")
      (description "Typical INFRARED GaAs LED")
      (fields (field (name "PUBLISHER") "Altium Limited"))
      (libsource (lib "Lib_Sch") (part "LED"))
    )
    (comp (ref "D187")
      (value "LED")
      (footprint "led_3mm")
      (description "Typical INFRARED GaAs LED")
      (fields (field (name "PUBLISHER") "Altium Limited"))
      (libsource (lib "Lib_Sch") (part "LED"))
    )
    (comp (ref "D188")
      (value "LED")
      (footprint "led_3mm")
      (description "Typical INFRARED GaAs LED")
      (fields (field (name "PUBLISHER") "Altium Limited"))
      (libsource (lib "Lib_Sch") (part "LED"))
    )
    (comp (ref "D189")
      (value "LED")
      (footprint "led_3mm")
      (description "Typical INFRARED GaAs LED")
      (fields (field (name "PUBLISHER") "Altium Limited"))
      (libsource (lib "Lib_Sch") (part "LED"))
    )
    (comp (ref "D190")
      (value "LED")
      (footprint "led_3mm")
      (description "Typical INFRARED GaAs LED")
      (fields (field (name "PUBLISHER") "Altium Limited"))
      (libsource (lib "Lib_Sch") (part "LED"))
    )
    (comp (ref "D191")
      (value "LED")
      (footprint "led_3mm")
      (description "Typical INFRARED GaAs LED")
      (fields (field (name "PUBLISHER") "Altium Limited"))
      (libsource (lib "Lib_Sch") (part "LED"))
    )
    (comp (ref "D192")
      (value "LED")
      (footprint "led_3mm")
      (description "Typical INFRARED GaAs LED")
      (fields (field (name "PUBLISHER") "Altium Limited"))
      (libsource (lib "Lib_Sch") (part "LED"))
    )
    (comp (ref "D193")
      (value "LED")
      (footprint "led_3mm")
      (description "Typical INFRARED GaAs LED")
      (fields (field (name "PUBLISHER") "Altium Limited"))
      (libsource (lib "Lib_Sch") (part "LED"))
    )
    (comp (ref "D194")
      (value "LED")
      (footprint "led_3mm")
      (description "Typical INFRARED GaAs LED")
      (fields (field (name "PUBLISHER") "Altium Limited"))
      (libsource (lib "Lib_Sch") (part "LED"))
    )
    (comp (ref "D195")
      (value "LED")
      (footprint "led_3mm")
      (description "Typical INFRARED GaAs LED")
      (fields (field (name "PUBLISHER") "Altium Limited"))
      (libsource (lib "Lib_Sch") (part "LED"))
    )
    (comp (ref "D196")
      (value "LED")
      (footprint "led_3mm")
      (description "Typical INFRARED GaAs LED")
      (fields (field (name "PUBLISHER") "Altium Limited"))
      (libsource (lib "Lib_Sch") (part "LED"))
    )
    (comp (ref "D197")
      (value "LED")
      (footprint "led_3mm")
      (description "Typical INFRARED GaAs LED")
      (fields (field (name "PUBLISHER") "Altium Limited"))
      (libsource (lib "Lib_Sch") (part "LED"))
    )
    (comp (ref "D198")
      (value "LED")
      (footprint "led_3mm")
      (description "Typical INFRARED GaAs LED")
      (fields (field (name "PUBLISHER") "Altium Limited"))
      (libsource (lib "Lib_Sch") (part "LED"))
    )
    (comp (ref "D199")
      (value "LED")
      (footprint "led_3mm")
      (description "Typical INFRARED GaAs LED")
      (fields (field (name "PUBLISHER") "Altium Limited"))
      (libsource (lib "Lib_Sch") (part "LED"))
    )
    (comp (ref "D200")
      (value "LED")
      (footprint "led_3mm")
      (description "Typical INFRARED GaAs LED")
      (fields (field (name "PUBLISHER") "Altium Limited"))
      (libsource (lib "Lib_Sch") (part "LED"))
    )
    (comp (ref "D201")
      (value "LED")
      (footprint "led_3mm")
      (description "Typical INFRARED GaAs LED")
      (fields (field (name "PUBLISHER") "Altium Limited"))
      (libsource (lib "Lib_Sch") (part "LED"))
    )
    (comp (ref "D202")
      (value "LED")
      (footprint "led_3mm")
      (description "Typical INFRARED GaAs LED")
      (fields (field (name "PUBLISHER") "Altium Limited"))
      (libsource (lib "Lib_Sch") (part "LED"))
    )
    (comp (ref "D203")
      (value "LED")
      (footprint "led_3mm")
      (description "Typical INFRARED GaAs LED")
      (fields (field (name "PUBLISHER") "Altium Limited"))
      (libsource (lib "Lib_Sch") (part "LED"))
    )
    (comp (ref "D204")
      (value "LED")
      (footprint "led_3mm")
      (description "Typical INFRARED GaAs LED")
      (fields (field (name "PUBLISHER") "Altium Limited"))
      (libsource (lib "Lib_Sch") (part "LED"))
    )
    (comp (ref "D205")
      (value "LED")
      (footprint "led_3mm")
      (description "Typical INFRARED GaAs LED")
      (fields (field (name "PUBLISHER") "Altium Limited"))
      (libsource (lib "Lib_Sch") (part "LED"))
    )
    (comp (ref "D206")
      (value "LED")
      (footprint "led_3mm")
      (description "Typical INFRARED GaAs LED")
      (fields (field (name "PUBLISHER") "Altium Limited"))
      (libsource (lib "Lib_Sch") (part "LED"))
    )
    (comp (ref "D207")
      (value "LED")
      (footprint "led_3mm")
      (description "Typical INFRARED GaAs LED")
      (fields (field (name "PUBLISHER") "Altium Limited"))
      (libsource (lib "Lib_Sch") (part "LED"))
    )
    (comp (ref "D208")
      (value "LED")
      (footprint "led_3mm")
      (description "Typical INFRARED GaAs LED")
      (fields (field (name "PUBLISHER") "Altium Limited"))
      (libsource (lib "Lib_Sch") (part "LED"))
    )
    (comp (ref "D209")
      (value "LED")
      (footprint "led_3mm")
      (description "Typical INFRARED GaAs LED")
      (fields (field (name "PUBLISHER") "Altium Limited"))
      (libsource (lib "Lib_Sch") (part "LED"))
    )
    (comp (ref "D210")
      (value "LED")
      (footprint "led_3mm")
      (description "Typical INFRARED GaAs LED")
      (fields (field (name "PUBLISHER") "Altium Limited"))
      (libsource (lib "Lib_Sch") (part "LED"))
    )
    (comp (ref "D211")
      (value "LED")
      (footprint "led_3mm")
      (description "Typical INFRARED GaAs LED")
      (fields (field (name "PUBLISHER") "Altium Limited"))
      (libsource (lib "Lib_Sch") (part "LED"))
    )
    (comp (ref "D212")
      (value "LED")
      (footprint "led_3mm")
      (description "Typical INFRARED GaAs LED")
      (fields (field (name "PUBLISHER") "Altium Limited"))
      (libsource (lib "Lib_Sch") (part "LED"))
    )
    (comp (ref "D213")
      (value "LED")
      (footprint "led_3mm")
      (description "Typical INFRARED GaAs LED")
      (fields (field (name "PUBLISHER") "Altium Limited"))
      (libsource (lib "Lib_Sch") (part "LED"))
    )
    (comp (ref "D214")
      (value "LED")
      (footprint "led_3mm")
      (description "Typical INFRARED GaAs LED")
      (fields (field (name "PUBLISHER") "Altium Limited"))
      (libsource (lib "Lib_Sch") (part "LED"))
    )
    (comp (ref "D215")
      (value "LED")
      (footprint "led_3mm")
      (description "Typical INFRARED GaAs LED")
      (fields (field (name "PUBLISHER") "Altium Limited"))
      (libsource (lib "Lib_Sch") (part "LED"))
    )
    (comp (ref "D216")
      (value "LED")
      (footprint "led_3mm")
      (description "Typical INFRARED GaAs LED")
      (fields (field (name "PUBLISHER") "Altium Limited"))
      (libsource (lib "Lib_Sch") (part "LED"))
    )
    (comp (ref "D217")
      (value "LED")
      (footprint "led_3mm")
      (description "Typical INFRARED GaAs LED")
      (fields (field (name "PUBLISHER") "Altium Limited"))
      (libsource (lib "Lib_Sch") (part "LED"))
    )
    (comp (ref "D218")
      (value "LED")
      (footprint "led_3mm")
      (description "Typical INFRARED GaAs LED")
      (fields (field (name "PUBLISHER") "Altium Limited"))
      (libsource (lib "Lib_Sch") (part "LED"))
    )
    (comp (ref "D219")
      (value "LED")
      (footprint "led_3mm")
      (description "Typical INFRARED GaAs LED")
      (fields (field (name "PUBLISHER") "Altium Limited"))
      (libsource (lib "Lib_Sch") (part "LED"))
    )
    (comp (ref "D220")
      (value "LED")
      (footprint "led_3mm")
      (description "Typical INFRARED GaAs LED")
      (fields (field (name "PUBLISHER") "Altium Limited"))
      (libsource (lib "Lib_Sch") (part "LED"))
    )
    (comp (ref "D221")
      (value "LED")
      (footprint "led_3mm")
      (description "Typical INFRARED GaAs LED")
      (fields (field (name "PUBLISHER") "Altium Limited"))
      (libsource (lib "Lib_Sch") (part "LED"))
    )
    (comp (ref "D222")
      (value "LED")
      (footprint "led_3mm")
      (description "Typical INFRARED GaAs LED")
      (fields (field (name "PUBLISHER") "Altium Limited"))
      (libsource (lib "Lib_Sch") (part "LED"))
    )
    (comp (ref "D223")
      (value "LED")
      (footprint "led_3mm")
      (description "Typical INFRARED GaAs LED")
      (fields (field (name "PUBLISHER") "Altium Limited"))
      (libsource (lib "Lib_Sch") (part "LED"))
    )
    (comp (ref "D224")
      (value "LED")
      (footprint "led_3mm")
      (description "Typical INFRARED GaAs LED")
      (fields (field (name "PUBLISHER") "Altium Limited"))
      (libsource (lib "Lib_Sch") (part "LED"))
    )
    (comp (ref "D225")
      (value "LED")
      (footprint "led_3mm")
      (description "Typical INFRARED GaAs LED")
      (fields (field (name "PUBLISHER") "Altium Limited"))
      (libsource (lib "Lib_Sch") (part "LED"))
    )
    (comp (ref "D226")
      (value "LED")
      (footprint "led_3mm")
      (description "Typical INFRARED GaAs LED")
      (fields (field (name "PUBLISHER") "Altium Limited"))
      (libsource (lib "Lib_Sch") (part "LED"))
    )
    (comp (ref "D227")
      (value "LED")
      (footprint "led_3mm")
      (description "Typical INFRARED GaAs LED")
      (fields (field (name "PUBLISHER") "Altium Limited"))
      (libsource (lib "Lib_Sch") (part "LED"))
    )
    (comp (ref "D228")
      (value "LED")
      (footprint "led_3mm")
      (description "Typical INFRARED GaAs LED")
      (fields (field (name "PUBLISHER") "Altium Limited"))
      (libsource (lib "Lib_Sch") (part "LED"))
    )
    (comp (ref "D229")
      (value "LED")
      (footprint "led_3mm")
      (description "Typical INFRARED GaAs LED")
      (fields (field (name "PUBLISHER") "Altium Limited"))
      (libsource (lib "Lib_Sch") (part "LED"))
    )
    (comp (ref "D230")
      (value "LED")
      (footprint "led_3mm")
      (description "Typical INFRARED GaAs LED")
      (fields (field (name "PUBLISHER") "Altium Limited"))
      (libsource (lib "Lib_Sch") (part "LED"))
    )
    (comp (ref "D231")
      (value "LED")
      (footprint "led_3mm")
      (description "Typical INFRARED GaAs LED")
      (fields (field (name "PUBLISHER") "Altium Limited"))
      (libsource (lib "Lib_Sch") (part "LED"))
    )
    (comp (ref "D232")
      (value "LED")
      (footprint "led_3mm")
      (description "Typical INFRARED GaAs LED")
      (fields (field (name "PUBLISHER") "Altium Limited"))
      (libsource (lib "Lib_Sch") (part "LED"))
    )
    (comp (ref "D233")
      (value "LED")
      (footprint "led_3mm")
      (description "Typical INFRARED GaAs LED")
      (fields (field (name "PUBLISHER") "Altium Limited"))
      (libsource (lib "Lib_Sch") (part "LED"))
    )
    (comp (ref "D234")
      (value "LED")
      (footprint "led_3mm")
      (description "Typical INFRARED GaAs LED")
      (fields (field (name "PUBLISHER") "Altium Limited"))
      (libsource (lib "Lib_Sch") (part "LED"))
    )
    (comp (ref "D235")
      (value "LED")
      (footprint "led_3mm")
      (description "Typical INFRARED GaAs LED")
      (fields (field (name "PUBLISHER") "Altium Limited"))
      (libsource (lib "Lib_Sch") (part "LED"))
    )
    (comp (ref "D236")
      (value "LED")
      (footprint "led_3mm")
      (description "Typical INFRARED GaAs LED")
      (fields (field (name "PUBLISHER") "Altium Limited"))
      (libsource (lib "Lib_Sch") (part "LED"))
    )
    (comp (ref "D237")
      (value "LED")
      (footprint "led_3mm")
      (description "Typical INFRARED GaAs LED")
      (fields (field (name "PUBLISHER") "Altium Limited"))
      (libsource (lib "Lib_Sch") (part "LED"))
    )
    (comp (ref "D238")
      (value "LED")
      (footprint "led_3mm")
      (description "Typical INFRARED GaAs LED")
      (fields (field (name "PUBLISHER") "Altium Limited"))
      (libsource (lib "Lib_Sch") (part "LED"))
    )
    (comp (ref "D239")
      (value "LED")
      (footprint "led_3mm")
      (description "Typical INFRARED GaAs LED")
      (fields (field (name "PUBLISHER") "Altium Limited"))
      (libsource (lib "Lib_Sch") (part "LED"))
    )
    (comp (ref "D240")
      (value "LED")
      (footprint "led_3mm")
      (description "Typical INFRARED GaAs LED")
      (fields (field (name "PUBLISHER") "Altium Limited"))
      (libsource (lib "Lib_Sch") (part "LED"))
    )
    (comp (ref "D241")
      (value "LED")
      (footprint "led_3mm")
      (description "Typical INFRARED GaAs LED")
      (fields (field (name "PUBLISHER") "Altium Limited"))
      (libsource (lib "Lib_Sch") (part "LED"))
    )
    (comp (ref "D242")
      (value "LED")
      (footprint "led_3mm")
      (description "Typical INFRARED GaAs LED")
      (fields (field (name "PUBLISHER") "Altium Limited"))
      (libsource (lib "Lib_Sch") (part "LED"))
    )
    (comp (ref "D243")
      (value "LED")
      (footprint "led_3mm")
      (description "Typical INFRARED GaAs LED")
      (fields (field (name "PUBLISHER") "Altium Limited"))
      (libsource (lib "Lib_Sch") (part "LED"))
    )
    (comp (ref "D244")
      (value "LED")
      (footprint "led_3mm")
      (description "Typical INFRARED GaAs LED")
      (fields (field (name "PUBLISHER") "Altium Limited"))
      (libsource (lib "Lib_Sch") (part "LED"))
    )
    (comp (ref "D245")
      (value "LED")
      (footprint "led_3mm")
      (description "Typical INFRARED GaAs LED")
      (fields (field (name "PUBLISHER") "Altium Limited"))
      (libsource (lib "Lib_Sch") (part "LED"))
    )
    (comp (ref "D246")
      (value "LED")
      (footprint "led_3mm")
      (description "Typical INFRARED GaAs LED")
      (fields (field (name "PUBLISHER") "Altium Limited"))
      (libsource (lib "Lib_Sch") (part "LED"))
    )
    (comp (ref "D247")
      (value "LED")
      (footprint "led_3mm")
      (description "Typical INFRARED GaAs LED")
      (fields (field (name "PUBLISHER") "Altium Limited"))
      (libsource (lib "Lib_Sch") (part "LED"))
    )
    (comp (ref "D248")
      (value "LED")
      (footprint "led_3mm")
      (description "Typical INFRARED GaAs LED")
      (fields (field (name "PUBLISHER") "Altium Limited"))
      (libsource (lib "Lib_Sch") (part "LED"))
    )
    (comp (ref "D249")
      (value "LED")
      (footprint "led_3mm")
      (description "Typical INFRARED GaAs LED")
      (fields (field (name "PUBLISHER") "Altium Limited"))
      (libsource (lib "Lib_Sch") (part "LED"))
    )
    (comp (ref "D250")
      (value "LED")
      (footprint "led_3mm")
      (description "Typical INFRARED GaAs LED")
      (fields (field (name "PUBLISHER") "Altium Limited"))
      (libsource (lib "Lib_Sch") (part "LED"))
    )
    (comp (ref "D251")
      (value "LED")
      (footprint "led_3mm")
      (description "Typical INFRARED GaAs LED")
      (fields (field (name "PUBLISHER") "Altium Limited"))
      (libsource (lib "Lib_Sch") (part "LED"))
    )
    (comp (ref "D252")
      (value "LED")
      (footprint "led_3mm")
      (description "Typical INFRARED GaAs LED")
      (fields (field (name "PUBLISHER") "Altium Limited"))
      (libsource (lib "Lib_Sch") (part "LED"))
    )
    (comp (ref "D253")
      (value "LED")
      (footprint "led_3mm")
      (description "Typical INFRARED GaAs LED")
      (fields (field (name "PUBLISHER") "Altium Limited"))
      (libsource (lib "Lib_Sch") (part "LED"))
    )
    (comp (ref "D254")
      (value "LED")
      (footprint "led_3mm")
      (description "Typical INFRARED GaAs LED")
      (fields (field (name "PUBLISHER") "Altium Limited"))
      (libsource (lib "Lib_Sch") (part "LED"))
    )
    (comp (ref "D255")
      (value "LED")
      (footprint "led_3mm")
      (description "Typical INFRARED GaAs LED")
      (fields (field (name "PUBLISHER") "Altium Limited"))
      (libsource (lib "Lib_Sch") (part "LED"))
    )
    (comp (ref "D256")
      (value "LED")
      (footprint "led_3mm")
      (description "Typical INFRARED GaAs LED")
      (fields (field (name "PUBLISHER") "Altium Limited"))
      (libsource (lib "Lib_Sch") (part "LED"))
    )
    (comp (ref "D257")
      (value "LED")
      (footprint "led_3mm")
      (description "Typical INFRARED GaAs LED")
      (fields (field (name "PUBLISHER") "Altium Limited"))
      (libsource (lib "Lib_Sch") (part "LED"))
    )
    (comp (ref "D258")
      (value "LED")
      (footprint "led_3mm")
      (description "Typical INFRARED GaAs LED")
      (fields (field (name "PUBLISHER") "Altium Limited"))
      (libsource (lib "Lib_Sch") (part "LED"))
    )
    (comp (ref "D259")
      (value "LED")
      (footprint "led_3mm")
      (description "Typical INFRARED GaAs LED")
      (fields (field (name "PUBLISHER") "Altium Limited"))
      (libsource (lib "Lib_Sch") (part "LED"))
    )
    (comp (ref "D260")
      (value "LED")
      (footprint "led_3mm")
      (description "Typical INFRARED GaAs LED")
      (fields (field (name "PUBLISHER") "Altium Limited"))
      (libsource (lib "Lib_Sch") (part "LED"))
    )
    (comp (ref "D261")
      (value "LED")
      (footprint "led_3mm")
      (description "Typical INFRARED GaAs LED")
      (fields (field (name "PUBLISHER") "Altium Limited"))
      (libsource (lib "Lib_Sch") (part "LED"))
    )
    (comp (ref "D262")
      (value "LED")
      (footprint "led_3mm")
      (description "Typical INFRARED GaAs LED")
      (fields (field (name "PUBLISHER") "Altium Limited"))
      (libsource (lib "Lib_Sch") (part "LED"))
    )
    (comp (ref "D263")
      (value "LED")
      (footprint "led_3mm")
      (description "Typical INFRARED GaAs LED")
      (fields (field (name "PUBLISHER") "Altium Limited"))
      (libsource (lib "Lib_Sch") (part "LED"))
    )
    (comp (ref "D264")
      (value "LED")
      (footprint "led_3mm")
      (description "Typical INFRARED GaAs LED")
      (fields (field (name "PUBLISHER") "Altium Limited"))
      (libsource (lib "Lib_Sch") (part "LED"))
    )
    (comp (ref "D265")
      (value "LED")
      (footprint "led_3mm")
      (description "Typical INFRARED GaAs LED")
      (fields (field (name "PUBLISHER") "Altium Limited"))
      (libsource (lib "Lib_Sch") (part "LED"))
    )
    (comp (ref "D266")
      (value "LED")
      (footprint "led_3mm")
      (description "Typical INFRARED GaAs LED")
      (fields (field (name "PUBLISHER") "Altium Limited"))
      (libsource (lib "Lib_Sch") (part "LED"))
    )
    (comp (ref "D267")
      (value "LED")
      (footprint "led_3mm")
      (description "Typical INFRARED GaAs LED")
      (fields (field (name "PUBLISHER") "Altium Limited"))
      (libsource (lib "Lib_Sch") (part "LED"))
    )
    (comp (ref "D268")
      (value "LED")
      (footprint "led_3mm")
      (description "Typical INFRARED GaAs LED")
      (fields (field (name "PUBLISHER") "Altium Limited"))
      (libsource (lib "Lib_Sch") (part "LED"))
    )
    (comp (ref "D269")
      (value "LED")
      (footprint "led_3mm")
      (description "Typical INFRARED GaAs LED")
      (fields (field (name "PUBLISHER") "Altium Limited"))
      (libsource (lib "Lib_Sch") (part "LED"))
    )
    (comp (ref "D270")
      (value "LED")
      (footprint "led_3mm")
      (description "Typical INFRARED GaAs LED")
      (fields (field (name "PUBLISHER") "Altium Limited"))
      (libsource (lib "Lib_Sch") (part "LED"))
    )
    (comp (ref "D271")
      (value "LED")
      (footprint "led_3mm")
      (description "Typical INFRARED GaAs LED")
      (fields (field (name "PUBLISHER") "Altium Limited"))
      (libsource (lib "Lib_Sch") (part "LED"))
    )
    (comp (ref "D272")
      (value "LED")
      (footprint "led_3mm")
      (description "Typical INFRARED GaAs LED")
      (fields (field (name "PUBLISHER") "Altium Limited"))
      (libsource (lib "Lib_Sch") (part "LED"))
    )
    (comp (ref "D273")
      (value "LED")
      (footprint "led_3mm")
      (description "Typical INFRARED GaAs LED")
      (fields (field (name "PUBLISHER") "Altium Limited"))
      (libsource (lib "Lib_Sch") (part "LED"))
    )
    (comp (ref "D274")
      (value "LED")
      (footprint "led_3mm")
      (description "Typical INFRARED GaAs LED")
      (fields (field (name "PUBLISHER") "Altium Limited"))
      (libsource (lib "Lib_Sch") (part "LED"))
    )
    (comp (ref "D275")
      (value "LED")
      (footprint "led_3mm")
      (description "Typical INFRARED GaAs LED")
      (fields (field (name "PUBLISHER") "Altium Limited"))
      (libsource (lib "Lib_Sch") (part "LED"))
    )
    (comp (ref "D276")
      (value "LED")
      (footprint "led_3mm")
      (description "Typical INFRARED GaAs LED")
      (fields (field (name "PUBLISHER") "Altium Limited"))
      (libsource (lib "Lib_Sch") (part "LED"))
    )
    (comp (ref "D277")
      (value "LED")
      (footprint "led_3mm")
      (description "Typical INFRARED GaAs LED")
      (fields (field (name "PUBLISHER") "Altium Limited"))
      (libsource (lib "Lib_Sch") (part "LED"))
    )
    (comp (ref "D278")
      (value "LED")
      (footprint "led_3mm")
      (description "Typical INFRARED GaAs LED")
      (fields (field (name "PUBLISHER") "Altium Limited"))
      (libsource (lib "Lib_Sch") (part "LED"))
    )
    (comp (ref "D279")
      (value "LED")
      (footprint "led_3mm")
      (description "Typical INFRARED GaAs LED")
      (fields (field (name "PUBLISHER") "Altium Limited"))
      (libsource (lib "Lib_Sch") (part "LED"))
    )
    (comp (ref "D280")
      (value "LED")
      (footprint "led_3mm")
      (description "Typical INFRARED GaAs LED")
      (fields (field (name "PUBLISHER") "Altium Limited"))
      (libsource (lib "Lib_Sch") (part "LED"))
    )
    (comp (ref "D281")
      (value "LED")
      (footprint "led_3mm")
      (description "Typical INFRARED GaAs LED")
      (fields (field (name "PUBLISHER") "Altium Limited"))
      (libsource (lib "Lib_Sch") (part "LED"))
    )
    (comp (ref "D282")
      (value "LED")
      (footprint "led_3mm")
      (description "Typical INFRARED GaAs LED")
      (fields (field (name "PUBLISHER") "Altium Limited"))
      (libsource (lib "Lib_Sch") (part "LED"))
    )
    (comp (ref "D283")
      (value "LED")
      (footprint "led_3mm")
      (description "Typical INFRARED GaAs LED")
      (fields (field (name "PUBLISHER") "Altium Limited"))
      (libsource (lib "Lib_Sch") (part "LED"))
    )
    (comp (ref "D284")
      (value "LED")
      (footprint "led_3mm")
      (description "Typical INFRARED GaAs LED")
      (fields (field (name "PUBLISHER") "Altium Limited"))
      (libsource (lib "Lib_Sch") (part "LED"))
    )
    (comp (ref "D285")
      (value "LED")
      (footprint "led_3mm")
      (description "Typical INFRARED GaAs LED")
      (fields (field (name "PUBLISHER") "Altium Limited"))
      (libsource (lib "Lib_Sch") (part "LED"))
    )
    (comp (ref "D286")
      (value "LED")
      (footprint "led_3mm")
      (description "Typical INFRARED GaAs LED")
      (fields (field (name "PUBLISHER") "Altium Limited"))
      (libsource (lib "Lib_Sch") (part "LED"))
    )
    (comp (ref "D287")
      (value "LED")
      (footprint "led_3mm")
      (description "Typical INFRARED GaAs LED")
      (fields (field (name "PUBLISHER") "Altium Limited"))
      (libsource (lib "Lib_Sch") (part "LED"))
    )
    (comp (ref "D288")
      (value "LED")
      (footprint "led_3mm")
      (description "Typical INFRARED GaAs LED")
      (fields (field (name "PUBLISHER") "Altium Limited"))
      (libsource (lib "Lib_Sch") (part "LED"))
    )
    (comp (ref "D289")
      (value "LED")
      (footprint "led_3mm")
      (description "Typical INFRARED GaAs LED")
      (fields (field (name "PUBLISHER") "Altium Limited"))
      (libsource (lib "Lib_Sch") (part "LED"))
    )
    (comp (ref "D290")
      (value "LED")
      (footprint "led_3mm")
      (description "Typical INFRARED GaAs LED")
      (fields (field (name "PUBLISHER") "Altium Limited"))
      (libsource (lib "Lib_Sch") (part "LED"))
    )
    (comp (ref "D291")
      (value "LED")
      (footprint "led_3mm")
      (description "Typical INFRARED GaAs LED")
      (fields (field (name "PUBLISHER") "Altium Limited"))
      (libsource (lib "Lib_Sch") (part "LED"))
    )
    (comp (ref "D292")
      (value "LED")
      (footprint "led_3mm")
      (description "Typical INFRARED GaAs LED")
      (fields (field (name "PUBLISHER") "Altium Limited"))
      (libsource (lib "Lib_Sch") (part "LED"))
    )
    (comp (ref "D293")
      (value "LED")
      (footprint "led_3mm")
      (description "Typical INFRARED GaAs LED")
      (fields (field (name "PUBLISHER") "Altium Limited"))
      (libsource (lib "Lib_Sch") (part "LED"))
    )
    (comp (ref "D294")
      (value "LED")
      (footprint "led_3mm")
      (description "Typical INFRARED GaAs LED")
      (fields (field (name "PUBLISHER") "Altium Limited"))
      (libsource (lib "Lib_Sch") (part "LED"))
    )
    (comp (ref "D295")
      (value "LED")
      (footprint "led_3mm")
      (description "Typical INFRARED GaAs LED")
      (fields (field (name "PUBLISHER") "Altium Limited"))
      (libsource (lib "Lib_Sch") (part "LED"))
    )
    (comp (ref "D296")
      (value "LED")
      (footprint "led_3mm")
      (description "Typical INFRARED GaAs LED")
      (fields (field (name "PUBLISHER") "Altium Limited"))
      (libsource (lib "Lib_Sch") (part "LED"))
    )
    (comp (ref "D297")
      (value "LED")
      (footprint "led_3mm")
      (description "Typical INFRARED GaAs LED")
      (fields (field (name "PUBLISHER") "Altium Limited"))
      (libsource (lib "Lib_Sch") (part "LED"))
    )
    (comp (ref "D298")
      (value "LED")
      (footprint "led_3mm")
      (description "Typical INFRARED GaAs LED")
      (fields (field (name "PUBLISHER") "Altium Limited"))
      (libsource (lib "Lib_Sch") (part "LED"))
    )
    (comp (ref "D299")
      (value "LED")
      (footprint "led_3mm")
      (description "Typical INFRARED GaAs LED")
      (fields (field (name "PUBLISHER") "Altium Limited"))
      (libsource (lib "Lib_Sch") (part "LED"))
    )
    (comp (ref "D300")
      (value "LED")
      (footprint "led_3mm")
      (description "Typical INFRARED GaAs LED")
      (fields (field (name "PUBLISHER") "Altium Limited"))
      (libsource (lib "Lib_Sch") (part "LED"))
    )
    (comp (ref "D301")
      (value "LED")
      (footprint "led_3mm")
      (description "Typical INFRARED GaAs LED")
      (fields (field (name "PUBLISHER") "Altium Limited"))
      (libsource (lib "Lib_Sch") (part "LED"))
    )
    (comp (ref "D302")
      (value "LED")
      (footprint "led_3mm")
      (description "Typical INFRARED GaAs LED")
      (fields (field (name "PUBLISHER") "Altium Limited"))
      (libsource (lib "Lib_Sch") (part "LED"))
    )
    (comp (ref "D303")
      (value "LED")
      (footprint "led_3mm")
      (description "Typical INFRARED GaAs LED")
      (fields (field (name "PUBLISHER") "Altium Limited"))
      (libsource (lib "Lib_Sch") (part "LED"))
    )
    (comp (ref "D304")
      (value "LED")
      (footprint "led_3mm")
      (description "Typical INFRARED GaAs LED")
      (fields (field (name "PUBLISHER") "Altium Limited"))
      (libsource (lib "Lib_Sch") (part "LED"))
    )
    (comp (ref "D305")
      (value "LED")
      (footprint "led_3mm")
      (description "Typical INFRARED GaAs LED")
      (fields (field (name "PUBLISHER") "Altium Limited"))
      (libsource (lib "Lib_Sch") (part "LED"))
    )
    (comp (ref "D306")
      (value "LED")
      (footprint "led_3mm")
      (description "Typical INFRARED GaAs LED")
      (fields (field (name "PUBLISHER") "Altium Limited"))
      (libsource (lib "Lib_Sch") (part "LED"))
    )
    (comp (ref "D307")
      (value "LED")
      (footprint "led_3mm")
      (description "Typical INFRARED GaAs LED")
      (fields (field (name "PUBLISHER") "Altium Limited"))
      (libsource (lib "Lib_Sch") (part "LED"))
    )
    (comp (ref "D308")
      (value "LED")
      (footprint "led_3mm")
      (description "Typical INFRARED GaAs LED")
      (fields (field (name "PUBLISHER") "Altium Limited"))
      (libsource (lib "Lib_Sch") (part "LED"))
    )
    (comp (ref "D309")
      (value "LED")
      (footprint "led_3mm")
      (description "Typical INFRARED GaAs LED")
      (fields (field (name "PUBLISHER") "Altium Limited"))
      (libsource (lib "Lib_Sch") (part "LED"))
    )
    (comp (ref "D310")
      (value "LED")
      (footprint "led_3mm")
      (description "Typical INFRARED GaAs LED")
      (fields (field (name "PUBLISHER") "Altium Limited"))
      (libsource (lib "Lib_Sch") (part "LED"))
    )
    (comp (ref "D311")
      (value "LED")
      (footprint "led_3mm")
      (description "Typical INFRARED GaAs LED")
      (fields (field (name "PUBLISHER") "Altium Limited"))
      (libsource (lib "Lib_Sch") (part "LED"))
    )
    (comp (ref "D312")
      (value "LED")
      (footprint "led_3mm")
      (description "Typical INFRARED GaAs LED")
      (fields (field (name "PUBLISHER") "Altium Limited"))
      (libsource (lib "Lib_Sch") (part "LED"))
    )
    (comp (ref "D313")
      (value "LED")
      (footprint "led_3mm")
      (description "Typical INFRARED GaAs LED")
      (fields (field (name "PUBLISHER") "Altium Limited"))
      (libsource (lib "Lib_Sch") (part "LED"))
    )
    (comp (ref "D314")
      (value "LED")
      (footprint "led_3mm")
      (description "Typical INFRARED GaAs LED")
      (fields (field (name "PUBLISHER") "Altium Limited"))
      (libsource (lib "Lib_Sch") (part "LED"))
    )
    (comp (ref "D315")
      (value "LED")
      (footprint "led_3mm")
      (description "Typical INFRARED GaAs LED")
      (fields (field (name "PUBLISHER") "Altium Limited"))
      (libsource (lib "Lib_Sch") (part "LED"))
    )
    (comp (ref "D316")
      (value "LED")
      (footprint "led_3mm")
      (description "Typical INFRARED GaAs LED")
      (fields (field (name "PUBLISHER") "Altium Limited"))
      (libsource (lib "Lib_Sch") (part "LED"))
    )
    (comp (ref "D317")
      (value "LED")
      (footprint "led_3mm")
      (description "Typical INFRARED GaAs LED")
      (fields (field (name "PUBLISHER") "Altium Limited"))
      (libsource (lib "Lib_Sch") (part "LED"))
    )
    (comp (ref "D318")
      (value "LED")
      (footprint "led_3mm")
      (description "Typical INFRARED GaAs LED")
      (fields (field (name "PUBLISHER") "Altium Limited"))
      (libsource (lib "Lib_Sch") (part "LED"))
    )
    (comp (ref "D319")
      (value "LED")
      (footprint "led_3mm")
      (description "Typical INFRARED GaAs LED")
      (fields (field (name "PUBLISHER") "Altium Limited"))
      (libsource (lib "Lib_Sch") (part "LED"))
    )
    (comp (ref "D320")
      (value "LED")
      (footprint "led_3mm")
      (description "Typical INFRARED GaAs LED")
      (fields (field (name "PUBLISHER") "Altium Limited"))
      (libsource (lib "Lib_Sch") (part "LED"))
    )
    (comp (ref "D321")
      (value "LED")
      (footprint "led_3mm")
      (description "Typical INFRARED GaAs LED")
      (fields (field (name "PUBLISHER") "Altium Limited"))
      (libsource (lib "Lib_Sch") (part "LED"))
    )
    (comp (ref "D322")
      (value "LED")
      (footprint "led_3mm")
      (description "Typical INFRARED GaAs LED")
      (fields (field (name "PUBLISHER") "Altium Limited"))
      (libsource (lib "Lib_Sch") (part "LED"))
    )
    (comp (ref "D323")
      (value "LED")
      (footprint "led_3mm")
      (description "Typical INFRARED GaAs LED")
      (fields (field (name "PUBLISHER") "Altium Limited"))
      (libsource (lib "Lib_Sch") (part "LED"))
    )
    (comp (ref "D324")
      (value "LED")
      (footprint "led_3mm")
      (description "Typical INFRARED GaAs LED")
      (fields (field (name "PUBLISHER") "Altium Limited"))
      (libsource (lib "Lib_Sch") (part "LED"))
    )
    (comp (ref "D325")
      (value "LED")
      (footprint "led_3mm")
      (description "Typical INFRARED GaAs LED")
      (fields (field (name "PUBLISHER") "Altium Limited"))
      (libsource (lib "Lib_Sch") (part "LED"))
    )
    (comp (ref "D326")
      (value "LED")
      (footprint "led_3mm")
      (description "Typical INFRARED GaAs LED")
      (fields (field (name "PUBLISHER") "Altium Limited"))
      (libsource (lib "Lib_Sch") (part "LED"))
    )
    (comp (ref "D327")
      (value "LED")
      (footprint "led_3mm")
      (description "Typical INFRARED GaAs LED")
      (fields (field (name "PUBLISHER") "Altium Limited"))
      (libsource (lib "Lib_Sch") (part "LED"))
    )
    (comp (ref "D328")
      (value "LED")
      (footprint "led_3mm")
      (description "Typical INFRARED GaAs LED")
      (fields (field (name "PUBLISHER") "Altium Limited"))
      (libsource (lib "Lib_Sch") (part "LED"))
    )
    (comp (ref "D329")
      (value "LED")
      (footprint "led_3mm")
      (description "Typical INFRARED GaAs LED")
      (fields (field (name "PUBLISHER") "Altium Limited"))
      (libsource (lib "Lib_Sch") (part "LED"))
    )
    (comp (ref "D330")
      (value "LED")
      (footprint "led_3mm")
      (description "Typical INFRARED GaAs LED")
      (fields (field (name "PUBLISHER") "Altium Limited"))
      (libsource (lib "Lib_Sch") (part "LED"))
    )
    (comp (ref "D331")
      (value "LED")
      (footprint "led_3mm")
      (description "Typical INFRARED GaAs LED")
      (fields (field (name "PUBLISHER") "Altium Limited"))
      (libsource (lib "Lib_Sch") (part "LED"))
    )
    (comp (ref "D332")
      (value "LED")
      (footprint "led_3mm")
      (description "Typical INFRARED GaAs LED")
      (fields (field (name "PUBLISHER") "Altium Limited"))
      (libsource (lib "Lib_Sch") (part "LED"))
    )
    (comp (ref "D333")
      (value "LED")
      (footprint "led_3mm")
      (description "Typical INFRARED GaAs LED")
      (fields (field (name "PUBLISHER") "Altium Limited"))
      (libsource (lib "Lib_Sch") (part "LED"))
    )
    (comp (ref "D334")
      (value "LED")
      (footprint "led_3mm")
      (description "Typical INFRARED GaAs LED")
      (fields (field (name "PUBLISHER") "Altium Limited"))
      (libsource (lib "Lib_Sch") (part "LED"))
    )
    (comp (ref "D335")
      (value "LED")
      (footprint "led_3mm")
      (description "Typical INFRARED GaAs LED")
      (fields (field (name "PUBLISHER") "Altium Limited"))
      (libsource (lib "Lib_Sch") (part "LED"))
    )
    (comp (ref "D336")
      (value "LED")
      (footprint "led_3mm")
      (description "Typical INFRARED GaAs LED")
      (fields (field (name "PUBLISHER") "Altium Limited"))
      (libsource (lib "Lib_Sch") (part "LED"))
    )
    (comp (ref "D337")
      (value "LED")
      (footprint "led_3mm")
      (description "Typical INFRARED GaAs LED")
      (fields (field (name "PUBLISHER") "Altium Limited"))
      (libsource (lib "Lib_Sch") (part "LED"))
    )
    (comp (ref "D338")
      (value "LED")
      (footprint "led_3mm")
      (description "Typical INFRARED GaAs LED")
      (fields (field (name "PUBLISHER") "Altium Limited"))
      (libsource (lib "Lib_Sch") (part "LED"))
    )
    (comp (ref "D339")
      (value "LED")
      (footprint "led_3mm")
      (description "Typical INFRARED GaAs LED")
      (fields (field (name "PUBLISHER") "Altium Limited"))
      (libsource (lib "Lib_Sch") (part "LED"))
    )
    (comp (ref "D340")
      (value "LED")
      (footprint "led_3mm")
      (description "Typical INFRARED GaAs LED")
      (fields (field (name "PUBLISHER") "Altium Limited"))
      (libsource (lib "Lib_Sch") (part "LED"))
    )
    (comp (ref "D341")
      (value "LED")
      (footprint "led_3mm")
      (description "Typical INFRARED GaAs LED")
      (fields (field (name "PUBLISHER") "Altium Limited"))
      (libsource (lib "Lib_Sch") (part "LED"))
    )
    (comp (ref "D342")
      (value "LED")
      (footprint "led_3mm")
      (description "Typical INFRARED GaAs LED")
      (fields (field (name "PUBLISHER") "Altium Limited"))
      (libsource (lib "Lib_Sch") (part "LED"))
    )
    (comp (ref "D343")
      (value "LED")
      (footprint "led_3mm")
      (description "Typical INFRARED GaAs LED")
      (fields (field (name "PUBLISHER") "Altium Limited"))
      (libsource (lib "Lib_Sch") (part "LED"))
    )
    (comp (ref "D344")
      (value "LED")
      (footprint "led_3mm")
      (description "Typical INFRARED GaAs LED")
      (fields (field (name "PUBLISHER") "Altium Limited"))
      (libsource (lib "Lib_Sch") (part "LED"))
    )
    (comp (ref "D345")
      (value "LED")
      (footprint "led_3mm")
      (description "Typical INFRARED GaAs LED")
      (fields (field (name "PUBLISHER") "Altium Limited"))
      (libsource (lib "Lib_Sch") (part "LED"))
    )
    (comp (ref "D346")
      (value "LED")
      (footprint "led_3mm")
      (description "Typical INFRARED GaAs LED")
      (fields (field (name "PUBLISHER") "Altium Limited"))
      (libsource (lib "Lib_Sch") (part "LED"))
    )
    (comp (ref "D347")
      (value "LED")
      (footprint "led_3mm")
      (description "Typical INFRARED GaAs LED")
      (fields (field (name "PUBLISHER") "Altium Limited"))
      (libsource (lib "Lib_Sch") (part "LED"))
    )
    (comp (ref "D348")
      (value "LED")
      (footprint "led_3mm")
      (description "Typical INFRARED GaAs LED")
      (fields (field (name "PUBLISHER") "Altium Limited"))
      (libsource (lib "Lib_Sch") (part "LED"))
    )
    (comp (ref "D349")
      (value "LED")
      (footprint "led_3mm")
      (description "Typical INFRARED GaAs LED")
      (fields (field (name "PUBLISHER") "Altium Limited"))
      (libsource (lib "Lib_Sch") (part "LED"))
    )
    (comp (ref "D350")
      (value "LED")
      (footprint "led_3mm")
      (description "Typical INFRARED GaAs LED")
      (fields (field (name "PUBLISHER") "Altium Limited"))
      (libsource (lib "Lib_Sch") (part "LED"))
    )
    (comp (ref "D351")
      (value "LED")
      (footprint "led_3mm")
      (description "Typical INFRARED GaAs LED")
      (fields (field (name "PUBLISHER") "Altium Limited"))
      (libsource (lib "Lib_Sch") (part "LED"))
    )
    (comp (ref "D352")
      (value "LED")
      (footprint "led_3mm")
      (description "Typical INFRARED GaAs LED")
      (fields (field (name "PUBLISHER") "Altium Limited"))
      (libsource (lib "Lib_Sch") (part "LED"))
    )
    (comp (ref "D353")
      (value "LED")
      (footprint "led_3mm")
      (description "Typical INFRARED GaAs LED")
      (fields (field (name "PUBLISHER") "Altium Limited"))
      (libsource (lib "Lib_Sch") (part "LED"))
    )
    (comp (ref "D354")
      (value "LED")
      (footprint "led_3mm")
      (description "Typical INFRARED GaAs LED")
      (fields (field (name "PUBLISHER") "Altium Limited"))
      (libsource (lib "Lib_Sch") (part "LED"))
    )
    (comp (ref "D355")
      (value "LED")
      (footprint "led_3mm")
      (description "Typical INFRARED GaAs LED")
      (fields (field (name "PUBLISHER") "Altium Limited"))
      (libsource (lib "Lib_Sch") (part "LED"))
    )
    (comp (ref "D356")
      (value "LED")
      (footprint "led_3mm")
      (description "Typical INFRARED GaAs LED")
      (fields (field (name "PUBLISHER") "Altium Limited"))
      (libsource (lib "Lib_Sch") (part "LED"))
    )
    (comp (ref "D357")
      (value "LED")
      (footprint "led_3mm")
      (description "Typical INFRARED GaAs LED")
      (fields (field (name "PUBLISHER") "Altium Limited"))
      (libsource (lib "Lib_Sch") (part "LED"))
    )
    (comp (ref "D358")
      (value "LED")
      (footprint "led_3mm")
      (description "Typical INFRARED GaAs LED")
      (fields (field (name "PUBLISHER") "Altium Limited"))
      (libsource (lib "Lib_Sch") (part "LED"))
    )
    (comp (ref "D359")
      (value "LED")
      (footprint "led_3mm")
      (description "Typical INFRARED GaAs LED")
      (fields (field (name "PUBLISHER") "Altium Limited"))
      (libsource (lib "Lib_Sch") (part "LED"))
    )
    (comp (ref "D360")
      (value "LED")
      (footprint "led_3mm")
      (description "Typical INFRARED GaAs LED")
      (fields (field (name "PUBLISHER") "Altium Limited"))
      (libsource (lib "Lib_Sch") (part "LED"))
    )
    (comp (ref "D361")
      (value "LED")
      (footprint "led_3mm")
      (description "Typical INFRARED GaAs LED")
      (fields (field (name "PUBLISHER") "Altium Limited"))
      (libsource (lib "Lib_Sch") (part "LED"))
    )
    (comp (ref "D362")
      (value "LED")
      (footprint "led_3mm")
      (description "Typical INFRARED GaAs LED")
      (fields (field (name "PUBLISHER") "Altium Limited"))
      (libsource (lib "Lib_Sch") (part "LED"))
    )
    (comp (ref "D363")
      (value "LED")
      (footprint "led_3mm")
      (description "Typical INFRARED GaAs LED")
      (fields (field (name "PUBLISHER") "Altium Limited"))
      (libsource (lib "Lib_Sch") (part "LED"))
    )
    (comp (ref "D364")
      (value "LED")
      (footprint "led_3mm")
      (description "Typical INFRARED GaAs LED")
      (fields (field (name "PUBLISHER") "Altium Limited"))
      (libsource (lib "Lib_Sch") (part "LED"))
    )
    (comp (ref "D365")
      (value "LED")
      (footprint "led_3mm")
      (description "Typical INFRARED GaAs LED")
      (fields (field (name "PUBLISHER") "Altium Limited"))
      (libsource (lib "Lib_Sch") (part "LED"))
    )
    (comp (ref "D366")
      (value "LED")
      (footprint "led_3mm")
      (description "Typical INFRARED GaAs LED")
      (fields (field (name "PUBLISHER") "Altium Limited"))
      (libsource (lib "Lib_Sch") (part "LED"))
    )
    (comp (ref "D367")
      (value "LED")
      (footprint "led_3mm")
      (description "Typical INFRARED GaAs LED")
      (fields (field (name "PUBLISHER") "Altium Limited"))
      (libsource (lib "Lib_Sch") (part "LED"))
    )
    (comp (ref "D368")
      (value "LED")
      (footprint "led_3mm")
      (description "Typical INFRARED GaAs LED")
      (fields (field (name "PUBLISHER") "Altium Limited"))
      (libsource (lib "Lib_Sch") (part "LED"))
    )
    (comp (ref "D369")
      (value "LED")
      (footprint "led_3mm")
      (description "Typical INFRARED GaAs LED")
      (fields (field (name "PUBLISHER") "Altium Limited"))
      (libsource (lib "Lib_Sch") (part "LED"))
    )
    (comp (ref "D370")
      (value "LED")
      (footprint "led_3mm")
      (description "Typical INFRARED GaAs LED")
      (fields (field (name "PUBLISHER") "Altium Limited"))
      (libsource (lib "Lib_Sch") (part "LED"))
    )
    (comp (ref "D371")
      (value "LED")
      (footprint "led_3mm")
      (description "Typical INFRARED GaAs LED")
      (fields (field (name "PUBLISHER") "Altium Limited"))
      (libsource (lib "Lib_Sch") (part "LED"))
    )
    (comp (ref "D372")
      (value "LED")
      (footprint "led_3mm")
      (description "Typical INFRARED GaAs LED")
      (fields (field (name "PUBLISHER") "Altium Limited"))
      (libsource (lib "Lib_Sch") (part "LED"))
    )
    (comp (ref "D373")
      (value "LED")
      (footprint "led_3mm")
      (description "Typical INFRARED GaAs LED")
      (fields (field (name "PUBLISHER") "Altium Limited"))
      (libsource (lib "Lib_Sch") (part "LED"))
    )
    (comp (ref "D374")
      (value "LED")
      (footprint "led_3mm")
      (description "Typical INFRARED GaAs LED")
      (fields (field (name "PUBLISHER") "Altium Limited"))
      (libsource (lib "Lib_Sch") (part "LED"))
    )
    (comp (ref "D375")
      (value "LED")
      (footprint "led_3mm")
      (description "Typical INFRARED GaAs LED")
      (fields (field (name "PUBLISHER") "Altium Limited"))
      (libsource (lib "Lib_Sch") (part "LED"))
    )
    (comp (ref "D376")
      (value "LED")
      (footprint "led_3mm")
      (description "Typical INFRARED GaAs LED")
      (fields (field (name "PUBLISHER") "Altium Limited"))
      (libsource (lib "Lib_Sch") (part "LED"))
    )
    (comp (ref "D377")
      (value "LED")
      (footprint "led_3mm")
      (description "Typical INFRARED GaAs LED")
      (fields (field (name "PUBLISHER") "Altium Limited"))
      (libsource (lib "Lib_Sch") (part "LED"))
    )
    (comp (ref "D378")
      (value "LED")
      (footprint "led_3mm")
      (description "Typical INFRARED GaAs LED")
      (fields (field (name "PUBLISHER") "Altium Limited"))
      (libsource (lib "Lib_Sch") (part "LED"))
    )
    (comp (ref "D379")
      (value "LED")
      (footprint "led_3mm")
      (description "Typical INFRARED GaAs LED")
      (fields (field (name "PUBLISHER") "Altium Limited"))
      (libsource (lib "Lib_Sch") (part "LED"))
    )
    (comp (ref "D380")
      (value "LED")
      (footprint "led_3mm")
      (description "Typical INFRARED GaAs LED")
      (fields (field (name "PUBLISHER") "Altium Limited"))
      (libsource (lib "Lib_Sch") (part "LED"))
    )
    (comp (ref "D381")
      (value "LED")
      (footprint "led_3mm")
      (description "Typical INFRARED GaAs LED")
      (fields (field (name "PUBLISHER") "Altium Limited"))
      (libsource (lib "Lib_Sch") (part "LED"))
    )
    (comp (ref "D382")
      (value "LED")
      (footprint "led_3mm")
      (description "Typical INFRARED GaAs LED")
      (fields (field (name "PUBLISHER") "Altium Limited"))
      (libsource (lib "Lib_Sch") (part "LED"))
    )
    (comp (ref "D383")
      (value "LED")
      (footprint "led_3mm")
      (description "Typical INFRARED GaAs LED")
      (fields (field (name "PUBLISHER") "Altium Limited"))
      (libsource (lib "Lib_Sch") (part "LED"))
    )
    (comp (ref "D384")
      (value "LED")
      (footprint "led_3mm")
      (description "Typical INFRARED GaAs LED")
      (fields (field (name "PUBLISHER") "Altium Limited"))
      (libsource (lib "Lib_Sch") (part "LED"))
    )
    (comp (ref "D385")
      (value "LED")
      (footprint "led_3mm")
      (description "Typical INFRARED GaAs LED")
      (fields (field (name "PUBLISHER") "Altium Limited"))
      (libsource (lib "Lib_Sch") (part "LED"))
    )
    (comp (ref "D386")
      (value "LED")
      (footprint "led_3mm")
      (description "Typical INFRARED GaAs LED")
      (fields (field (name "PUBLISHER") "Altium Limited"))
      (libsource (lib "Lib_Sch") (part "LED"))
    )
    (comp (ref "D387")
      (value "LED")
      (footprint "led_3mm")
      (description "Typical INFRARED GaAs LED")
      (fields (field (name "PUBLISHER") "Altium Limited"))
      (libsource (lib "Lib_Sch") (part "LED"))
    )
    (comp (ref "D388")
      (value "LED")
      (footprint "led_3mm")
      (description "Typical INFRARED GaAs LED")
      (fields (field (name "PUBLISHER") "Altium Limited"))
      (libsource (lib "Lib_Sch") (part "LED"))
    )
    (comp (ref "D389")
      (value "LED")
      (footprint "led_3mm")
      (description "Typical INFRARED GaAs LED")
      (fields (field (name "PUBLISHER") "Altium Limited"))
      (libsource (lib "Lib_Sch") (part "LED"))
    )
    (comp (ref "D390")
      (value "LED")
      (footprint "led_3mm")
      (description "Typical INFRARED GaAs LED")
      (fields (field (name "PUBLISHER") "Altium Limited"))
      (libsource (lib "Lib_Sch") (part "LED"))
    )
    (comp (ref "D391")
      (value "LED")
      (footprint "led_3mm")
      (description "Typical INFRARED GaAs LED")
      (fields (field (name "PUBLISHER") "Altium Limited"))
      (libsource (lib "Lib_Sch") (part "LED"))
    )
    (comp (ref "D392")
      (value "LED")
      (footprint "led_3mm")
      (description "Typical INFRARED GaAs LED")
      (fields (field (name "PUBLISHER") "Altium Limited"))
      (libsource (lib "Lib_Sch") (part "LED"))
    )
    (comp (ref "D393")
      (value "LED")
      (footprint "led_3mm")
      (description "Typical INFRARED GaAs LED")
      (fields (field (name "PUBLISHER") "Altium Limited"))
      (libsource (lib "Lib_Sch") (part "LED"))
    )
    (comp (ref "D394")
      (value "LED")
      (footprint "led_3mm")
      (description "Typical INFRARED GaAs LED")
      (fields (field (name "PUBLISHER") "Altium Limited"))
      (libsource (lib "Lib_Sch") (part "LED"))
    )
    (comp (ref "D395")
      (value "LED")
      (footprint "led_3mm")
      (description "Typical INFRARED GaAs LED")
      (fields (field (name "PUBLISHER") "Altium Limited"))
      (libsource (lib "Lib_Sch") (part "LED"))
    )
    (comp (ref "D396")
      (value "LED")
      (footprint "led_3mm")
      (description "Typical INFRARED GaAs LED")
      (fields (field (name "PUBLISHER") "Altium Limited"))
      (libsource (lib "Lib_Sch") (part "LED"))
    )
    (comp (ref "D397")
      (value "LED")
      (footprint "led_3mm")
      (description "Typical INFRARED GaAs LED")
      (fields (field (name "PUBLISHER") "Altium Limited"))
      (libsource (lib "Lib_Sch") (part "LED"))
    )
    (comp (ref "D398")
      (value "LED")
      (footprint "led_3mm")
      (description "Typical INFRARED GaAs LED")
      (fields (field (name "PUBLISHER") "Altium Limited"))
      (libsource (lib "Lib_Sch") (part "LED"))
    )
  )
  (nets
    (net (code "1") (name "/MATRIX_A1") (class "Default")
      (node (ref "D115") (pin "A") (pinfunction "A_A") (pintype "passive"))
      (node (ref "D141") (pin "A") (pinfunction "A_A") (pintype "passive"))
      (node (ref "D167") (pin "A") (pinfunction "A_A") (pintype "passive"))
      (node (ref "D193") (pin "A") (pinfunction "A_A") (pintype "passive"))
    )
    (net (code "2") (name "/MATRIX_A2") (class "Default")
      (node (ref "D116") (pin "A") (pinfunction "A_A") (pintype "passive"))
      (node (ref "D142") (pin "A") (pinfunction "A_A") (pintype "passive"))
      (node (ref "D168") (pin "A") (pinfunction "A_A") (pintype "passive"))
      (node (ref "D194") (pin "A") (pinfunction "A_A") (pintype "passive"))
      (node (ref "D219") (pin "A") (pinfunction "A_A") (pintype "passive"))
      (node (ref "D243") (pin "A") (pinfunction "A_A") (pintype "passive"))
      (node (ref "D67") (pin "A") (pinfunction "A_A") (pintype "passive"))
      (node (ref "D91") (pin "A") (pinfunction "A_A") (pintype "passive"))
    )
    (net (code "3") (name "/MATRIX_A3") (class "Default")
      (node (ref "D117") (pin "A") (pinfunction "A_A") (pintype "passive"))
      (node (ref "D143") (pin "A") (pinfunction "A_A") (pintype "passive"))
      (node (ref "D169") (pin "A") (pinfunction "A_A") (pintype "passive"))
      (node (ref "D195") (pin "A") (pinfunction "A_A") (pintype "passive"))
      (node (ref "D220") (pin "A") (pinfunction "A_A") (pintype "passive"))
      (node (ref "D244") (pin "A") (pinfunction "A_A") (pintype "passive"))
      (node (ref "D267") (pin "A") (pinfunction "A_A") (pintype "passive"))
      (node (ref "D45") (pin "A") (pinfunction "A_A") (pintype "passive"))
      (node (ref "D68") (pin "A") (pinfunction "A_A") (pintype "passive"))
      (node (ref "D92") (pin "A") (pinfunction "A_A") (pintype "passive"))
    )
    (net (code "4") (name "/MATRIX_A4") (class "Default")
      (node (ref "D118") (pin "A") (pinfunction "A_A") (pintype "passive"))
      (node (ref "D144") (pin "A") (pinfunction "A_A") (pintype "passive"))
      (node (ref "D170") (pin "A") (pinfunction "A_A") (pintype "passive"))
      (node (ref "D196") (pin "A") (pinfunction "A_A") (pintype "passive"))
      (node (ref "D221") (pin "A") (pinfunction "A_A") (pintype "passive"))
      (node (ref "D245") (pin "A") (pinfunction "A_A") (pintype "passive"))
      (node (ref "D25") (pin "A") (pinfunction "A_A") (pintype "passive"))
      (node (ref "D268") (pin "A") (pinfunction "A_A") (pintype "passive"))
      (node (ref "D289") (pin "A") (pinfunction "A_A") (pintype "passive"))
      (node (ref "D46") (pin "A") (pinfunction "A_A") (pintype "passive"))
      (node (ref "D69") (pin "A") (pinfunction "A_A") (pintype "passive"))
      (node (ref "D93") (pin "A") (pinfunction "A_A") (pintype "passive"))
    )
    (net (code "5") (name "/MATRIX_A5") (class "Default")
      (node (ref "D119") (pin "A") (pinfunction "A_A") (pintype "passive"))
      (node (ref "D145") (pin "A") (pinfunction "A_A") (pintype "passive"))
      (node (ref "D171") (pin "A") (pinfunction "A_A") (pintype "passive"))
      (node (ref "D197") (pin "A") (pinfunction "A_A") (pintype "passive"))
      (node (ref "D222") (pin "A") (pinfunction "A_A") (pintype "passive"))
      (node (ref "D246") (pin "A") (pinfunction "A_A") (pintype "passive"))
      (node (ref "D26") (pin "A") (pinfunction "A_A") (pintype "passive"))
      (node (ref "D269") (pin "A") (pinfunction "A_A") (pintype "passive"))
      (node (ref "D290") (pin "A") (pinfunction "A_A") (pintype "passive"))
      (node (ref "D309") (pin "A") (pinfunction "A_A") (pintype "passive"))
      (node (ref "D47") (pin "A") (pinfunction "A_A") (pintype "passive"))
      (node (ref "D70") (pin "A") (pinfunction "A_A") (pintype "passive"))
      (node (ref "D9") (pin "A") (pinfunction "A_A") (pintype "passive"))
      (node (ref "D94") (pin "A") (pinfunction "A_A") (pintype "passive"))
    )
    (net (code "6") (name "/MATRIX_A6") (class "Default")
      (node (ref "D10") (pin "A") (pinfunction "A_A") (pintype "passive"))
      (node (ref "D120") (pin "A") (pinfunction "A_A") (pintype "passive"))
      (node (ref "D146") (pin "A") (pinfunction "A_A") (pintype "passive"))
      (node (ref "D172") (pin "A") (pinfunction "A_A") (pintype "passive"))
      (node (ref "D198") (pin "A") (pinfunction "A_A") (pintype "passive"))
      (node (ref "D223") (pin "A") (pinfunction "A_A") (pintype "passive"))
      (node (ref "D247") (pin "A") (pinfunction "A_A") (pintype "passive"))
      (node (ref "D27") (pin "A") (pinfunction "A_A") (pintype "passive"))
      (node (ref "D270") (pin "A") (pinfunction "A_A") (pintype "passive"))
      (node (ref "D291") (pin "A") (pinfunction "A_A") (pintype "passive"))
      (node (ref "D310") (pin "A") (pinfunction "A_A") (pintype "passive"))
      (node (ref "D327") (pin "A") (pinfunction "A_A") (pintype "passive"))
      (node (ref "D48") (pin "A") (pinfunction "A_A") (pintype "passive"))
      (node (ref "D71") (pin "A") (pinfunction "A_A") (pintype "passive"))
      (node (ref "D95") (pin "A") (pinfunction "A_A") (pintype "passive"))
    )
    (net (code "7") (name "/MATRIX_A7") (class "Default")
      (node (ref "D1") (pin "A") (pinfunction "A_A") (pintype "passive"))
      (node (ref "D11") (pin "A") (pinfunction "A_A") (pintype "passive"))
      (node (ref "D121") (pin "A") (pinfunction "A_A") (pintype "passive"))
      (node (ref "D147") (pin "A") (pinfunction "A_A") (pintype "passive"))
      (node (ref "D173") (pin "A") (pinfunction "A_A") (pintype "passive"))
      (node (ref "D199") (pin "A") (pinfunction "A_A") (pintype "passive"))
      (node (ref "D224") (pin "A") (pinfunction "A_A") (pintype "passive"))
      (node (ref "D248") (pin "A") (pinfunction "A_A") (pintype "passive"))
      (node (ref "D271") (pin "A") (pinfunction "A_A") (pintype "passive"))
      (node (ref "D28") (pin "A") (pinfunction "A_A") (pintype "passive"))
      (node (ref "D292") (pin "A") (pinfunction "A_A") (pintype "passive"))
      (node (ref "D311") (pin "A") (pinfunction "A_A") (pintype "passive"))
      (node (ref "D328") (pin "A") (pinfunction "A_A") (pintype "passive"))
      (node (ref "D343") (pin "A") (pinfunction "A_A") (pintype "passive"))
      (node (ref "D49") (pin "A") (pinfunction "A_A") (pintype "passive"))
      (node (ref "D72") (pin "A") (pinfunction "A_A") (pintype "passive"))
      (node (ref "D96") (pin "A") (pinfunction "A_A") (pintype "passive"))
    )
    (net (code "8") (name "/MATRIX_A8") (class "Default")
      (node (ref "D12") (pin "A") (pinfunction "A_A") (pintype "passive"))
      (node (ref "D122") (pin "A") (pinfunction "A_A") (pintype "passive"))
      (node (ref "D148") (pin "A") (pinfunction "A_A") (pintype "passive"))
      (node (ref "D174") (pin "A") (pinfunction "A_A") (pintype "passive"))
      (node (ref "D2") (pin "A") (pinfunction "A_A") (pintype "passive"))
      (node (ref "D200") (pin "A") (pinfunction "A_A") (pintype "passive"))
      (node (ref "D225") (pin "A") (pinfunction "A_A") (pintype "passive"))
      (node (ref "D249") (pin "A") (pinfunction "A_A") (pintype "passive"))
      (node (ref "D272") (pin "A") (pinfunction "A_A") (pintype "passive"))
      (node (ref "D29") (pin "A") (pinfunction "A_A") (pintype "passive"))
      (node (ref "D293") (pin "A") (pinfunction "A_A") (pintype "passive"))
      (node (ref "D312") (pin "A") (pinfunction "A_A") (pintype "passive"))
      (node (ref "D329") (pin "A") (pinfunction "A_A") (pintype "passive"))
      (node (ref "D344") (pin "A") (pinfunction "A_A") (pintype "passive"))
      (node (ref "D357") (pin "A") (pinfunction "A_A") (pintype "passive"))
      (node (ref "D50") (pin "A") (pinfunction "A_A") (pintype "passive"))
      (node (ref "D73") (pin "A") (pinfunction "A_A") (pintype "passive"))
      (node (ref "D97") (pin "A") (pinfunction "A_A") (pintype "passive"))
    )
    (net (code "9") (name "/MATRIX_A9") (class "Default")
      (node (ref "D123") (pin "A") (pinfunction "A_A") (pintype "passive"))
      (node (ref "D13") (pin "A") (pinfunction "A_A") (pintype "passive"))
      (node (ref "D149") (pin "A") (pinfunction "A_A") (pintype "passive"))
      (node (ref "D175") (pin "A") (pinfunction "A_A") (pintype "passive"))
      (node (ref "D201") (pin "A") (pinfunction "A_A") (pintype "passive"))
      (node (ref "D226") (pin "A") (pinfunction "A_A") (pintype "passive"))
      (node (ref "D250") (pin "A") (pinfunction "A_A") (pintype "passive"))
      (node (ref "D273") (pin "A") (pinfunction "A_A") (pintype "passive"))
      (node (ref "D294") (pin "A") (pinfunction "A_A") (pintype "passive"))
      (node (ref "D3") (pin "A") (pinfunction "A_A") (pintype "passive"))
      (node (ref "D30") (pin "A") (pinfunction "A_A") (pintype "passive"))
      (node (ref "D313") (pin "A") (pinfunction "A_A") (pintype "passive"))
      (node (ref "D330") (pin "A") (pinfunction "A_A") (pintype "passive"))
      (node (ref "D345") (pin "A") (pinfunction "A_A") (pintype "passive"))
      (node (ref "D358") (pin "A") (pinfunction "A_A") (pintype "passive"))
      (node (ref "D369") (pin "A") (pinfunction "A_A") (pintype "passive"))
      (node (ref "D51") (pin "A") (pinfunction "A_A") (pintype "passive"))
      (node (ref "D74") (pin "A") (pinfunction "A_A") (pintype "passive"))
      (node (ref "D98") (pin "A") (pinfunction "A_A") (pintype "passive"))
    )
    (net (code "10") (name "/MATRIX_A10") (class "Default")
      (node (ref "D124") (pin "A") (pinfunction "A_A") (pintype "passive"))
      (node (ref "D14") (pin "A") (pinfunction "A_A") (pintype "passive"))
      (node (ref "D150") (pin "A") (pinfunction "A_A") (pintype "passive"))
      (node (ref "D176") (pin "A") (pinfunction "A_A") (pintype "passive"))
      (node (ref "D202") (pin "A") (pinfunction "A_A") (pintype "passive"))
      (node (ref "D227") (pin "A") (pinfunction "A_A") (pintype "passive"))
      (node (ref "D251") (pin "A") (pinfunction "A_A") (pintype "passive"))
      (node (ref "D274") (pin "A") (pinfunction "A_A") (pintype "passive"))
      (node (ref "D295") (pin "A") (pinfunction "A_A") (pintype "passive"))
      (node (ref "D31") (pin "A") (pinfunction "A_A") (pintype "passive"))
      (node (ref "D314") (pin "A") (pinfunction "A_A") (pintype "passive"))
      (node (ref "D331") (pin "A") (pinfunction "A_A") (pintype "passive"))
      (node (ref "D346") (pin "A") (pinfunction "A_A") (pintype "passive"))
      (node (ref "D359") (pin "A") (pinfunction "A_A") (pintype "passive"))
      (node (ref "D370") (pin "A") (pinfunction "A_A") (pintype "passive"))
      (node (ref "D379") (pin "A") (pinfunction "A_A") (pintype "passive"))
      (node (ref "D4") (pin "A") (pinfunction "A_A") (pintype "passive"))
      (node (ref "D52") (pin "A") (pinfunction "A_A") (pintype "passive"))
      (node (ref "D75") (pin "A") (pinfunction "A_A") (pintype "passive"))
      (node (ref "D99") (pin "A") (pinfunction "A_A") (pintype "passive"))
    )
    (net (code "11") (name "/MATRIX_A11") (class "Default")
      (node (ref "D100") (pin "A") (pinfunction "A_A") (pintype "passive"))
      (node (ref "D125") (pin "A") (pinfunction "A_A") (pintype "passive"))
      (node (ref "D15") (pin "A") (pinfunction "A_A") (pintype "passive"))
      (node (ref "D151") (pin "A") (pinfunction "A_A") (pintype "passive"))
      (node (ref "D177") (pin "A") (pinfunction "A_A") (pintype "passive"))
      (node (ref "D203") (pin "A") (pinfunction "A_A") (pintype "passive"))
      (node (ref "D228") (pin "A") (pinfunction "A_A") (pintype "passive"))
      (node (ref "D252") (pin "A") (pinfunction "A_A") (pintype "passive"))
      (node (ref "D275") (pin "A") (pinfunction "A_A") (pintype "passive"))
      (node (ref "D296") (pin "A") (pinfunction "A_A") (pintype "passive"))
      (node (ref "D315") (pin "A") (pinfunction "A_A") (pintype "passive"))
      (node (ref "D32") (pin "A") (pinfunction "A_A") (pintype "passive"))
      (node (ref "D332") (pin "A") (pinfunction "A_A") (pintype "passive"))
      (node (ref "D347") (pin "A") (pinfunction "A_A") (pintype "passive"))
      (node (ref "D360") (pin "A") (pinfunction "A_A") (pintype "passive"))
      (node (ref "D371") (pin "A") (pinfunction "A_A") (pintype "passive"))
      (node (ref "D380") (pin "A") (pinfunction "A_A") (pintype "passive"))
      (node (ref "D387") (pin "A") (pinfunction "A_A") (pintype "passive"))
      (node (ref "D53") (pin "A") (pinfunction "A_A") (pintype "passive"))
      (node (ref "D76") (pin "A") (pinfunction "A_A") (pintype "passive"))
    )
    (net (code "12") (name "/MATRIX_A12") (class "Default")
      (node (ref "D101") (pin "A") (pinfunction "A_A") (pintype "passive"))
      (node (ref "D126") (pin "A") (pinfunction "A_A") (pintype "passive"))
      (node (ref "D152") (pin "A") (pinfunction "A_A") (pintype "passive"))
      (node (ref "D16") (pin "A") (pinfunction "A_A") (pintype "passive"))
      (node (ref "D178") (pin "A") (pinfunction "A_A") (pintype "passive"))
      (node (ref "D204") (pin "A") (pinfunction "A_A") (pintype "passive"))
      (node (ref "D229") (pin "A") (pinfunction "A_A") (pintype "passive"))
      (node (ref "D253") (pin "A") (pinfunction "A_A") (pintype "passive"))
      (node (ref "D276") (pin "A") (pinfunction "A_A") (pintype "passive"))
      (node (ref "D297") (pin "A") (pinfunction "A_A") (pintype "passive"))
      (node (ref "D316") (pin "A") (pinfunction "A_A") (pintype "passive"))
      (node (ref "D33") (pin "A") (pinfunction "A_A") (pintype "passive"))
      (node (ref "D333") (pin "A") (pinfunction "A_A") (pintype "passive"))
      (node (ref "D348") (pin "A") (pinfunction "A_A") (pintype "passive"))
      (node (ref "D361") (pin "A") (pinfunction "A_A") (pintype "passive"))
      (node (ref "D372") (pin "A") (pinfunction "A_A") (pintype "passive"))
      (node (ref "D381") (pin "A") (pinfunction "A_A") (pintype "passive"))
      (node (ref "D388") (pin "A") (pinfunction "A_A") (pintype "passive"))
      (node (ref "D393") (pin "A") (pinfunction "A_A") (pintype "passive"))
      (node (ref "D54") (pin "A") (pinfunction "A_A") (pintype "passive"))
      (node (ref "D77") (pin "A") (pinfunction "A_A") (pintype "passive"))
    )
    (net (code "13") (name "/MATRIX_A13") (class "Default")
      (node (ref "D102") (pin "A") (pinfunction "A_A") (pintype "passive"))
      (node (ref "D127") (pin "A") (pinfunction "A_A") (pintype "passive"))
      (node (ref "D153") (pin "A") (pinfunction "A_A") (pintype "passive"))
      (node (ref "D179") (pin "A") (pinfunction "A_A") (pintype "passive"))
      (node (ref "D205") (pin "A") (pinfunction "A_A") (pintype "passive"))
      (node (ref "D230") (pin "A") (pinfunction "A_A") (pintype "passive"))
      (node (ref "D254") (pin "A") (pinfunction "A_A") (pintype "passive"))
      (node (ref "D277") (pin "A") (pinfunction "A_A") (pintype "passive"))
      (node (ref "D298") (pin "A") (pinfunction "A_A") (pintype "passive"))
      (node (ref "D317") (pin "A") (pinfunction "A_A") (pintype "passive"))
      (node (ref "D334") (pin "A") (pinfunction "A_A") (pintype "passive"))
      (node (ref "D34") (pin "A") (pinfunction "A_A") (pintype "passive"))
      (node (ref "D349") (pin "A") (pinfunction "A_A") (pintype "passive"))
      (node (ref "D362") (pin "A") (pinfunction "A_A") (pintype "passive"))
      (node (ref "D373") (pin "A") (pinfunction "A_A") (pintype "passive"))
      (node (ref "D382") (pin "A") (pinfunction "A_A") (pintype "passive"))
      (node (ref "D389") (pin "A") (pinfunction "A_A") (pintype "passive"))
      (node (ref "D394") (pin "A") (pinfunction "A_A") (pintype "passive"))
      (node (ref "D397") (pin "A") (pinfunction "A_A") (pintype "passive"))
      (node (ref "D55") (pin "A") (pinfunction "A_A") (pintype "passive"))
      (node (ref "D78") (pin "A") (pinfunction "A_A") (pintype "passive"))
    )
    (net (code "14") (name "/MATRIX_A14") (class "Default")
      (node (ref "D103") (pin "A") (pinfunction "A_A") (pintype "passive"))
      (node (ref "D128") (pin "A") (pinfunction "A_A") (pintype "passive"))
      (node (ref "D154") (pin "A") (pinfunction "A_A") (pintype "passive"))
      (node (ref "D180") (pin "A") (pinfunction "A_A") (pintype "passive"))
      (node (ref "D206") (pin "A") (pinfunction "A_A") (pintype "passive"))
      (node (ref "D231") (pin "A") (pinfunction "A_A") (pintype "passive"))
      (node (ref "D255") (pin "A") (pinfunction "A_A") (pintype "passive"))
      (node (ref "D278") (pin "A") (pinfunction "A_A") (pintype "passive"))
      (node (ref "D299") (pin "A") (pinfunction "A_A") (pintype "passive"))
      (node (ref "D318") (pin "A") (pinfunction "A_A") (pintype "passive"))
      (node (ref "D335") (pin "A") (pinfunction "A_A") (pintype "passive"))
      (node (ref "D35") (pin "A") (pinfunction "A_A") (pintype "passive"))
      (node (ref "D350") (pin "A") (pinfunction "A_A") (pintype "passive"))
      (node (ref "D363") (pin "A") (pinfunction "A_A") (pintype "passive"))
      (node (ref "D374") (pin "A") (pinfunction "A_A") (pintype "passive"))
      (node (ref "D383") (pin "A") (pinfunction "A_A") (pintype "passive"))
      (node (ref "D390") (pin "A") (pinfunction "A_A") (pintype "passive"))
      (node (ref "D395") (pin "A") (pinfunction "A_A") (pintype "passive"))
      (node (ref "D398") (pin "A") (pinfunction "A_A") (pintype "passive"))
      (node (ref "D56") (pin "A") (pinfunction "A_A") (pintype "passive"))
      (node (ref "D79") (pin "A") (pinfunction "A_A") (pintype "passive"))
    )
    (net (code "15") (name "/MATRIX_A15") (class "Default")
      (node (ref "D104") (pin "A") (pinfunction "A_A") (pintype "passive"))
      (node (ref "D129") (pin "A") (pinfunction "A_A") (pintype "passive"))
      (node (ref "D155") (pin "A") (pinfunction "A_A") (pintype "passive"))
      (node (ref "D17") (pin "A") (pinfunction "A_A") (pintype "passive"))
      (node (ref "D181") (pin "A") (pinfunction "A_A") (pintype "passive"))
      (node (ref "D207") (pin "A") (pinfunction "A_A") (pintype "passive"))
      (node (ref "D232") (pin "A") (pinfunction "A_A") (pintype "passive"))
      (node (ref "D256") (pin "A") (pinfunction "A_A") (pintype "passive"))
      (node (ref "D279") (pin "A") (pinfunction "A_A") (pintype "passive"))
      (node (ref "D300") (pin "A") (pinfunction "A_A") (pintype "passive"))
      (node (ref "D319") (pin "A") (pinfunction "A_A") (pintype "passive"))
      (node (ref "D336") (pin "A") (pinfunction "A_A") (pintype "passive"))
      (node (ref "D351") (pin "A") (pinfunction "A_A") (pintype "passive"))
      (node (ref "D36") (pin "A") (pinfunction "A_A") (pintype "passive"))
      (node (ref "D364") (pin "A") (pinfunction "A_A") (pintype "passive"))
      (node (ref "D375") (pin "A") (pinfunction "A_A") (pintype "passive"))
      (node (ref "D384") (pin "A") (pinfunction "A_A") (pintype "passive"))
      (node (ref "D391") (pin "A") (pinfunction "A_A") (pintype "passive"))
      (node (ref "D396") (pin "A") (pinfunction "A_A") (pintype "passive"))
      (node (ref "D57") (pin "A") (pinfunction "A_A") (pintype "passive"))
      (node (ref "D80") (pin "A") (pinfunction "A_A") (pintype "passive"))
    )
    (net (code "16") (name "/MATRIX_A16") (class "Default")
      (node (ref "D105") (pin "A") (pinfunction "A_A") (pintype "passive"))
      (node (ref "D130") (pin "A") (pinfunction "A_A") (pintype "passive"))
      (node (ref "D156") (pin "A") (pinfunction "A_A") (pintype "passive"))
      (node (ref "D18") (pin "A") (pinfunction "A_A") (pintype "passive"))
      (node (ref "D182") (pin "A") (pinfunction "A_A") (pintype "passive"))
      (node (ref "D208") (pin "A") (pinfunction "A_A") (pintype "passive"))
      (node (ref "D233") (pin "A") (pinfunction "A_A") (pintype "passive"))
      (node (ref "D257") (pin "A") (pinfunction "A_A") (pintype "passive"))
      (node (ref "D280") (pin "A") (pinfunction "A_A") (pintype "passive"))
      (node (ref "D301") (pin "A") (pinfunction "A_A") (pintype "passive"))
      (node (ref "D320") (pin "A") (pinfunction "A_A") (pintype "passive"))
      (node (ref "D337") (pin "A") (pinfunction "A_A") (pintype "passive"))
      (node (ref "D352") (pin "A") (pinfunction "A_A") (pintype "passive"))
      (node (ref "D365") (pin "A") (pinfunction "A_A") (pintype "passive"))
      (node (ref "D37") (pin "A") (pinfunction "A_A") (pintype "passive"))
      (node (ref "D376") (pin "A") (pinfunction "A_A") (pintype "passive"))
      (node (ref "D385") (pin "A") (pinfunction "A_A") (pintype "passive"))
      (node (ref "D392") (pin "A") (pinfunction "A_A") (pintype "passive"))
      (node (ref "D58") (pin "A") (pinfunction "A_A") (pintype "passive"))
      (node (ref "D81") (pin "A") (pinfunction "A_A") (pintype "passive"))
    )
    (net (code "17") (name "/MATRIX_A17") (class "Default")
      (node (ref "D106") (pin "A") (pinfunction "A_A") (pintype "passive"))
      (node (ref "D131") (pin "A") (pinfunction "A_A") (pintype "passive"))
      (node (ref "D157") (pin "A") (pinfunction "A_A") (pintype "passive"))
      (node (ref "D183") (pin "A") (pinfunction "A_A") (pintype "passive"))
      (node (ref "D19") (pin "A") (pinfunction "A_A") (pintype "passive"))
      (node (ref "D209") (pin "A") (pinfunction "A_A") (pintype "passive"))
      (node (ref "D234") (pin "A") (pinfunction "A_A") (pintype "passive"))
      (node (ref "D258") (pin "A") (pinfunction "A_A") (pintype "passive"))
      (node (ref "D281") (pin "A") (pinfunction "A_A") (pintype "passive"))
      (node (ref "D302") (pin "A") (pinfunction "A_A") (pintype "passive"))
      (node (ref "D321") (pin "A") (pinfunction "A_A") (pintype "passive"))
      (node (ref "D338") (pin "A") (pinfunction "A_A") (pintype "passive"))
      (node (ref "D353") (pin "A") (pinfunction "A_A") (pintype "passive"))
      (node (ref "D366") (pin "A") (pinfunction "A_A") (pintype "passive"))
      (node (ref "D377") (pin "A") (pinfunction "A_A") (pintype "passive"))
      (node (ref "D38") (pin "A") (pinfunction "A_A") (pintype "passive"))
      (node (ref "D386") (pin "A") (pinfunction "A_A") (pintype "passive"))
      (node (ref "D5") (pin "A") (pinfunction "A_A") (pintype "passive"))
      (node (ref "D59") (pin "A") (pinfunction "A_A") (pintype "passive"))
      (node (ref "D82") (pin "A") (pinfunction "A_A") (pintype "passive"))
    )
    (net (code "18") (name "/MATRIX_A18") (class "Default")
      (node (ref "D107") (pin "A") (pinfunction "A_A") (pintype "passive"))
      (node (ref "D132") (pin "A") (pinfunction "A_A") (pintype "passive"))
      (node (ref "D158") (pin "A") (pinfunction "A_A") (pintype "passive"))
      (node (ref "D184") (pin "A") (pinfunction "A_A") (pintype "passive"))
      (node (ref "D20") (pin "A") (pinfunction "A_A") (pintype "passive"))
      (node (ref "D210") (pin "A") (pinfunction "A_A") (pintype "passive"))
      (node (ref "D235") (pin "A") (pinfunction "A_A") (pintype "passive"))
      (node (ref "D259") (pin "A") (pinfunction "A_A") (pintype "passive"))
      (node (ref "D282") (pin "A") (pinfunction "A_A") (pintype "passive"))
      (node (ref "D303") (pin "A") (pinfunction "A_A") (pintype "passive"))
      (node (ref "D322") (pin "A") (pinfunction "A_A") (pintype "passive"))
      (node (ref "D339") (pin "A") (pinfunction "A_A") (pintype "passive"))
      (node (ref "D354") (pin "A") (pinfunction "A_A") (pintype "passive"))
      (node (ref "D367") (pin "A") (pinfunction "A_A") (pintype "passive"))
      (node (ref "D378") (pin "A") (pinfunction "A_A") (pintype "passive"))
      (node (ref "D39") (pin "A") (pinfunction "A_A") (pintype "passive"))
      (node (ref "D6") (pin "A") (pinfunction "A_A") (pintype "passive"))
      (node (ref "D60") (pin "A") (pinfunction "A_A") (pintype "passive"))
      (node (ref "D83") (pin "A") (pinfunction "A_A") (pintype "passive"))
    )
    (net (code "19") (name "/MATRIX_A19") (class "Default")
      (node (ref "D108") (pin "A") (pinfunction "A_A") (pintype "passive"))
      (node (ref "D133") (pin "A") (pinfunction "A_A") (pintype "passive"))
      (node (ref "D159") (pin "A") (pinfunction "A_A") (pintype "passive"))
      (node (ref "D185") (pin "A") (pinfunction "A_A") (pintype "passive"))
      (node (ref "D21") (pin "A") (pinfunction "A_A") (pintype "passive"))
      (node (ref "D211") (pin "A") (pinfunction "A_A") (pintype "passive"))
      (node (ref "D236") (pin "A") (pinfunction "A_A") (pintype "passive"))
      (node (ref "D260") (pin "A") (pinfunction "A_A") (pintype "passive"))
      (node (ref "D283") (pin "A") (pinfunction "A_A") (pintype "passive"))
      (node (ref "D304") (pin "A") (pinfunction "A_A") (pintype "passive"))
      (node (ref "D323") (pin "A") (pinfunction "A_A") (pintype "passive"))
      (node (ref "D340") (pin "A") (pinfunction "A_A") (pintype "passive"))
      (node (ref "D355") (pin "A") (pinfunction "A_A") (pintype "passive"))
      (node (ref "D368") (pin "A") (pinfunction "A_A") (pintype "passive"))
      (node (ref "D40") (pin "A") (pinfunction "A_A") (pintype "passive"))
      (node (ref "D61") (pin "A") (pinfunction "A_A") (pintype "passive"))
      (node (ref "D7") (pin "A") (pinfunction "A_A") (pintype "passive"))
      (node (ref "D84") (pin "A") (pinfunction "A_A") (pintype "passive"))
    )
    (net (code "20") (name "/MATRIX_A20") (class "Default")
      (node (ref "D109") (pin "A") (pinfunction "A_A") (pintype "passive"))
      (node (ref "D134") (pin "A") (pinfunction "A_A") (pintype "passive"))
      (node (ref "D160") (pin "A") (pinfunction "A_A") (pintype "passive"))
      (node (ref "D186") (pin "A") (pinfunction "A_A") (pintype "passive"))
      (node (ref "D212") (pin "A") (pinfunction "A_A") (pintype "passive"))
      (node (ref "D22") (pin "A") (pinfunction "A_A") (pintype "passive"))
      (node (ref "D237") (pin "A") (pinfunction "A_A") (pintype "passive"))
      (node (ref "D261") (pin "A") (pinfunction "A_A") (pintype "passive"))
      (node (ref "D284") (pin "A") (pinfunction "A_A") (pintype "passive"))
      (node (ref "D305") (pin "A") (pinfunction "A_A") (pintype "passive"))
      (node (ref "D324") (pin "A") (pinfunction "A_A") (pintype "passive"))
      (node (ref "D341") (pin "A") (pinfunction "A_A") (pintype "passive"))
      (node (ref "D356") (pin "A") (pinfunction "A_A") (pintype "passive"))
      (node (ref "D41") (pin "A") (pinfunction "A_A") (pintype "passive"))
      (node (ref "D62") (pin "A") (pinfunction "A_A") (pintype "passive"))
      (node (ref "D8") (pin "A") (pinfunction "A_A") (pintype "passive"))
      (node (ref "D85") (pin "A") (pinfunction "A_A") (pintype "passive"))
    )
    (net (code "21") (name "/MATRIX_A21") (class "Default")
      (node (ref "D110") (pin "A") (pinfunction "A_A") (pintype "passive"))
      (node (ref "D135") (pin "A") (pinfunction "A_A") (pintype "passive"))
      (node (ref "D161") (pin "A") (pinfunction "A_A") (pintype "passive"))
      (node (ref "D187") (pin "A") (pinfunction "A_A") (pintype "passive"))
      (node (ref "D213") (pin "A") (pinfunction "A_A") (pintype "passive"))
      (node (ref "D23") (pin "A") (pinfunction "A_A") (pintype "passive"))
      (node (ref "D238") (pin "A") (pinfunction "A_A") (pintype "passive"))
      (node (ref "D262") (pin "A") (pinfunction "A_A") (pintype "passive"))
      (node (ref "D285") (pin "A") (pinfunction "A_A") (pintype "passive"))
      (node (ref "D306") (pin "A") (pinfunction "A_A") (pintype "passive"))
      (node (ref "D325") (pin "A") (pinfunction "A_A") (pintype "passive"))
      (node (ref "D342") (pin "A") (pinfunction "A_A") (pintype "passive"))
      (node (ref "D42") (pin "A") (pinfunction "A_A") (pintype "passive"))
      (node (ref "D63") (pin "A") (pinfunction "A_A") (pintype "passive"))
      (node (ref "D86") (pin "A") (pinfunction "A_A") (pintype "passive"))
    )
    (net (code "22") (name "/MATRIX_A22") (class "Default")
      (node (ref "D111") (pin "A") (pinfunction "A_A") (pintype "passive"))
      (node (ref "D136") (pin "A") (pinfunction "A_A") (pintype "passive"))
      (node (ref "D162") (pin "A") (pinfunction "A_A") (pintype "passive"))
      (node (ref "D188") (pin "A") (pinfunction "A_A") (pintype "passive"))
      (node (ref "D214") (pin "A") (pinfunction "A_A") (pintype "passive"))
      (node (ref "D239") (pin "A") (pinfunction "A_A") (pintype "passive"))
      (node (ref "D24") (pin "A") (pinfunction "A_A") (pintype "passive"))
      (node (ref "D263") (pin "A") (pinfunction "A_A") (pintype "passive"))
      (node (ref "D286") (pin "A") (pinfunction "A_A") (pintype "passive"))
      (node (ref "D307") (pin "A") (pinfunction "A_A") (pintype "passive"))
      (node (ref "D326") (pin "A") (pinfunction "A_A") (pintype "passive"))
      (node (ref "D43") (pin "A") (pinfunction "A_A") (pintype "passive"))
      (node (ref "D64") (pin "A") (pinfunction "A_A") (pintype "passive"))
      (node (ref "D87") (pin "A") (pinfunction "A_A") (pintype "passive"))
    )
    (net (code "23") (name "/MATRIX_A23") (class "Default")
      (node (ref "D112") (pin "A") (pinfunction "A_A") (pintype "passive"))
      (node (ref "D137") (pin "A") (pinfunction "A_A") (pintype "passive"))
      (node (ref "D163") (pin "A") (pinfunction "A_A") (pintype "passive"))
      (node (ref "D189") (pin "A") (pinfunction "A_A") (pintype "passive"))
      (node (ref "D215") (pin "A") (pinfunction "A_A") (pintype "passive"))
      (node (ref "D240") (pin "A") (pinfunction "A_A") (pintype "passive"))
      (node (ref "D264") (pin "A") (pinfunction "A_A") (pintype "passive"))
      (node (ref "D287") (pin "A") (pinfunction "A_A") (pintype "passive"))
      (node (ref "D308") (pin "A") (pinfunction "A_A") (pintype "passive"))
      (node (ref "D44") (pin "A") (pinfunction "A_A") (pintype "passive"))
      (node (ref "D65") (pin "A") (pinfunction "A_A") (pintype "passive"))
      (node (ref "D88") (pin "A") (pinfunction "A_A") (pintype "passive"))
    )
    (net (code "24") (name "/MATRIX_A24") (class "Default")
      (node (ref "D113") (pin "A") (pinfunction "A_A") (pintype "passive"))
      (node (ref "D138") (pin "A") (pinfunction "A_A") (pintype "passive"))
      (node (ref "D164") (pin "A") (pinfunction "A_A") (pintype "passive"))
      (node (ref "D190") (pin "A") (pinfunction "A_A") (pintype "passive"))
      (node (ref "D216") (pin "A") (pinfunction "A_A") (pintype "passive"))
      (node (ref "D241") (pin "A") (pinfunction "A_A") (pintype "passive"))
      (node (ref "D265") (pin "A") (pinfunction "A_A") (pintype "passive"))
      (node (ref "D288") (pin "A") (pinfunction "A_A") (pintype "passive"))
      (node (ref "D66") (pin "A") (pinfunction "A_A") (pintype "passive"))
      (node (ref "D89") (pin "A") (pinfunction "A_A") (pintype "passive"))
    )
    (net (code "25") (name "/MATRIX_A25") (class "Default")
      (node (ref "D114") (pin "A") (pinfunction "A_A") (pintype "passive"))
      (node (ref "D139") (pin "A") (pinfunction "A_A") (pintype "passive"))
      (node (ref "D165") (pin "A") (pinfunction "A_A") (pintype "passive"))
      (node (ref "D191") (pin "A") (pinfunction "A_A") (pintype "passive"))
      (node (ref "D217") (pin "A") (pinfunction "A_A") (pintype "passive"))
      (node (ref "D242") (pin "A") (pinfunction "A_A") (pintype "passive"))
      (node (ref "D266") (pin "A") (pinfunction "A_A") (pintype "passive"))
      (node (ref "D90") (pin "A") (pinfunction "A_A") (pintype "passive"))
    )
    (net (code "26") (name "/MATRIX_A26") (class "Default")
      (node (ref "D140") (pin "A") (pinfunction "A_A") (pintype "passive"))
      (node (ref "D166") (pin "A") (pinfunction "A_A") (pintype "passive"))
      (node (ref "D192") (pin "A") (pinfunction "A_A") (pintype "passive"))
      (node (ref "D218") (pin "A") (pinfunction "A_A") (pintype "passive"))
    )
    (net (code "27") (name "/MATRIX_K1") (class "Default")
      (node (ref "D1") (pin "K") (pinfunction "K_K") (pintype "passive"))
      (node (ref "D2") (pin "K") (pinfunction "K_K") (pintype "passive"))
      (node (ref "D3") (pin "K") (pinfunction "K_K") (pintype "passive"))
      (node (ref "D4") (pin "K") (pinfunction "K_K") (pintype "passive"))
      (node (ref "D5") (pin "K") (pinfunction "K_K") (pintype "passive"))
      (node (ref "D6") (pin "K") (pinfunction "K_K") (pintype "passive"))
      (node (ref "D7") (pin "K") (pinfunction "K_K") (pintype "passive"))
      (node (ref "D8") (pin "K") (pinfunction "K_K") (pintype "passive"))
    )
    (net (code "28") (name "/MATRIX_K2") (class "Default")
      (node (ref "D10") (pin "K") (pinfunction "K_K") (pintype "passive"))
      (node (ref "D11") (pin "K") (pinfunction "K_K") (pintype "passive"))
      (node (ref "D12") (pin "K") (pinfunction "K_K") (pintype "passive"))
      (node (ref "D13") (pin "K") (pinfunction "K_K") (pintype "passive"))
      (node (ref "D14") (pin "K") (pinfunction "K_K") (pintype "passive"))
      (node (ref "D15") (pin "K") (pinfunction "K_K") (pintype "passive"))
      (node (ref "D16") (pin "K") (pinfunction "K_K") (pintype "passive"))
      (node (ref "D17") (pin "K") (pinfunction "K_K") (pintype "passive"))
      (node (ref "D18") (pin "K") (pinfunction "K_K") (pintype "passive"))
      (node (ref "D19") (pin "K") (pinfunction "K_K") (pintype "passive"))
      (node (ref "D20") (pin "K") (pinfunction "K_K") (pintype "passive"))
      (node (ref "D21") (pin "K") (pinfunction "K_K") (pintype "passive"))
      (node (ref "D22") (pin "K") (pinfunction "K_K") (pintype "passive"))
      (node (ref "D23") (pin "K") (pinfunction "K_K") (pintype "passive"))
      (node (ref "D24") (pin "K") (pinfunction "K_K") (pintype "passive"))
      (node (ref "D9") (pin "K") (pinfunction "K_K") (pintype "passive"))
    )
    (net (code "29") (name "/MATRIX_K3") (class "Default")
      (node (ref "D25") (pin "K") (pinfunction "K_K") (pintype "passive"))
      (node (ref "D26") (pin "K") (pinfunction "K_K") (pintype "passive"))
      (node (ref "D27") (pin "K") (pinfunction "K_K") (pintype "passive"))
      (node (ref "D28") (pin "K") (pinfunction "K_K") (pintype "passive"))
      (node (ref "D29") (pin "K") (pinfunction "K_K") (pintype "passive"))
      (node (ref "D30") (pin "K") (pinfunction "K_K") (pintype "passive"))
      (node (ref "D31") (pin "K") (pinfunction "K_K") (pintype "passive"))
      (node (ref "D32") (pin "K") (pinfunction "K_K") (pintype "passive"))
      (node (ref "D33") (pin "K") (pinfunction "K_K") (pintype "passive"))
      (node (ref "D34") (pin "K") (pinfunction "K_K") (pintype "passive"))
      (node (ref "D35") (pin "K") (pinfunction "K_K") (pintype "passive"))
      (node (ref "D36") (pin "K") (pinfunction "K_K") (pintype "passive"))
      (node (ref "D37") (pin "K") (pinfunction "K_K") (pintype "passive"))
      (node (ref "D38") (pin "K") (pinfunction "K_K") (pintype "passive"))
      (node (ref "D39") (pin "K") (pinfunction "K_K") (pintype "passive"))
      (node (ref "D40") (pin "K") (pinfunction "K_K") (pintype "passive"))
      (node (ref "D41") (pin "K") (pinfunction "K_K") (pintype "passive"))
      (node (ref "D42") (pin "K") (pinfunction "K_K") (pintype "passive"))
      (node (ref "D43") (pin "K") (pinfunction "K_K") (pintype "passive"))
      (node (ref "D44") (pin "K") (pinfunction "K_K") (pintype "passive"))
    )
    (net (code "30") (name "/MATRIX_K4") (class "Default")
      (node (ref "D45") (pin "K") (pinfunction "K_K") (pintype "passive"))
      (node (ref "D46") (pin "K") (pinfunction "K_K") (pintype "passive"))
      (node (ref "D47") (pin "K") (pinfunction "K_K") (pintype "passive"))
      (node (ref "D48") (pin "K") (pinfunction "K_K") (pintype "passive"))
      (node (ref "D49") (pin "K") (pinfunction "K_K") (pintype "passive"))
      (node (ref "D50") (pin "K") (pinfunction "K_K") (pintype "passive"))
      (node (ref "D51") (pin "K") (pinfunction "K_K") (pintype "passive"))
      (node (ref "D52") (pin "K") (pinfunction "K_K") (pintype "passive"))
      (node (ref "D53") (pin "K") (pinfunction "K_K") (pintype "passive"))
      (node (ref "D54") (pin "K") (pinfunction "K_K") (pintype "passive"))
      (node (ref "D55") (pin "K") (pinfunction "K_K") (pintype "passive"))
      (node (ref "D56") (pin "K") (pinfunction "K_K") (pintype "passive"))
      (node (ref "D57") (pin "K") (pinfunction "K_K") (pintype "passive"))
      (node (ref "D58") (pin "K") (pinfunction "K_K") (pintype "passive"))
      (node (ref "D59") (pin "K") (pinfunction "K_K") (pintype "passive"))
      (node (ref "D60") (pin "K") (pinfunction "K_K") (pintype "passive"))
      (node (ref "D61") (pin "K") (pinfunction "K_K") (pintype "passive"))
      (node (ref "D62") (pin "K") (pinfunction "K_K") (pintype "passive"))
      (node (ref "D63") (pin "K") (pinfunction "K_K") (pintype "passive"))
      (node (ref "D64") (pin "K") (pinfunction "K_K") (pintype "passive"))
      (node (ref "D65") (pin "K") (pinfunction "K_K") (pintype "passive"))
      (node (ref "D66") (pin "K") (pinfunction "K_K") (pintype "passive"))
    )
    (net (code "31") (name "/MATRIX_K5") (class "Default")
      (node (ref "D67") (pin "K") (pinfunction "K_K") (pintype "passive"))
      (node (ref "D68") (pin "K") (pinfunction "K_K") (pintype "passive"))
      (node (ref "D69") (pin "K") (pinfunction "K_K") (pintype "passive"))
      (node (ref "D70") (pin "K") (pinfunction "K_K") (pintype "passive"))
      (node (ref "D71") (pin "K") (pinfunction "K_K") (pintype "passive"))
      (node (ref "D72") (pin "K") (pinfunction "K_K") (pintype "passive"))
      (node (ref "D73") (pin "K") (pinfunction "K_K") (pintype "passive"))
      (node (ref "D74") (pin "K") (pinfunction "K_K") (pintype "passive"))
      (node (ref "D75") (pin "K") (pinfunction "K_K") (pintype "passive"))
      (node (ref "D76") (pin "K") (pinfunction "K_K") (pintype "passive"))
      (node (ref "D77") (pin "K") (pinfunction "K_K") (pintype "passive"))
      (node (ref "D78") (pin "K") (pinfunction "K_K") (pintype "passive"))
      (node (ref "D79") (pin "K") (pinfunction "K_K") (pintype "passive"))
      (node (ref "D80") (pin "K") (pinfunction "K_K") (pintype "passive"))
      (node (ref "D81") (pin "K") (pinfunction "K_K") (pintype "passive"))
      (node (ref "D82") (pin "K") (pinfunction "K_K") (pintype "passive"))
      (node (ref "D83") (pin "K") (pinfunction "K_K") (pintype "passive"))
      (node (ref "D84") (pin "K") (pinfunction "K_K") (pintype "passive"))
      (node (ref "D85") (pin "K") (pinfunction "K_K") (pintype "passive"))
      (node (ref "D86") (pin "K") (pinfunction "K_K") (pintype "passive"))
      (node (ref "D87") (pin "K") (pinfunction "K_K") (pintype "passive"))
      (node (ref "D88") (pin "K") (pinfunction "K_K") (pintype "passive"))
      (node (ref "D89") (pin "K") (pinfunction "K_K") (pintype "passive"))
      (node (ref "D90") (pin "K") (pinfunction "K_K") (pintype "passive"))
    )
    (net (code "32") (name "/MATRIX_K6") (class "Default")
      (node (ref "D100") (pin "K") (pinfunction "K_K") (pintype "passive"))
      (node (ref "D101") (pin "K") (pinfunction "K_K") (pintype "passive"))
      (node (ref "D102") (pin "K") (pinfunction "K_K") (pintype "passive"))
      (node (ref "D103") (pin "K") (pinfunction "K_K") (pintype "passive"))
      (node (ref "D104") (pin "K") (pinfunction "K_K") (pintype "passive"))
      (node (ref "D105") (pin "K") (pinfunction "K_K") (pintype "passive"))
      (node (ref "D106") (pin "K") (pinfunction "K_K") (pintype "passive"))
      (node (ref "D107") (pin "K") (pinfunction "K_K") (pintype "passive"))
      (node (ref "D108") (pin "K") (pinfunction "K_K") (pintype "passive"))
      (node (ref "D109") (pin "K") (pinfunction "K_K") (pintype "passive"))
      (node (ref "D110") (pin "K") (pinfunction "K_K") (pintype "passive"))
      (node (ref "D111") (pin "K") (pinfunction "K_K") (pintype "passive"))
      (node (ref "D112") (pin "K") (pinfunction "K_K") (pintype "passive"))
      (node (ref "D113") (pin "K") (pinfunction "K_K") (pintype "passive"))
      (node (ref "D114") (pin "K") (pinfunction "K_K") (pintype "passive"))
      (node (ref "D91") (pin "K") (pinfunction "K_K") (pintype "passive"))
      (node (ref "D92") (pin "K") (pinfunction "K_K") (pintype "passive"))
      (node (ref "D93") (pin "K") (pinfunction "K_K") (pintype "passive"))
      (node (ref "D94") (pin "K") (pinfunction "K_K") (pintype "passive"))
      (node (ref "D95") (pin "K") (pinfunction "K_K") (pintype "passive"))
      (node (ref "D96") (pin "K") (pinfunction "K_K") (pintype "passive"))
      (node (ref "D97") (pin "K") (pinfunction "K_K") (pintype "passive"))
      (node (ref "D98") (pin "K") (pinfunction "K_K") (pintype "passive"))
      (node (ref "D99") (pin "K") (pinfunction "K_K") (pintype "passive"))
    )
    (net (code "33") (name "/MATRIX_K7") (class "Default")
      (node (ref "D115") (pin "K") (pinfunction "K_K") (pintype "passive"))
      (node (ref "D116") (pin "K") (pinfunction "K_K") (pintype "passive"))
      (node (ref "D117") (pin "K") (pinfunction "K_K") (pintype "passive"))
      (node (ref "D118") (pin "K") (pinfunction "K_K") (pintype "passive"))
      (node (ref "D119") (pin "K") (pinfunction "K_K") (pintype "passive"))
      (node (ref "D120") (pin "K") (pinfunction "K_K") (pintype "passive"))
      (node (ref "D121") (pin "K") (pinfunction "K_K") (pintype "passive"))
      (node (ref "D122") (pin "K") (pinfunction "K_K") (pintype "passive"))
      (node (ref "D123") (pin "K") (pinfunction "K_K") (pintype "passive"))
      (node (ref "D124") (pin "K") (pinfunction "K_K") (pintype "passive"))
      (node (ref "D125") (pin "K") (pinfunction "K_K") (pintype "passive"))
      (node (ref "D126") (pin "K") (pinfunction "K_K") (pintype "passive"))
      (node (ref "D127") (pin "K") (pinfunction "K_K") (pintype "passive"))
      (node (ref "D128") (pin "K") (pinfunction "K_K") (pintype "passive"))
      (node (ref "D129") (pin "K") (pinfunction "K_K") (pintype "passive"))
      (node (ref "D130") (pin "K") (pinfunction "K_K") (pintype "passive"))
      (node (ref "D131") (pin "K") (pinfunction "K_K") (pintype "passive"))
      (node (ref "D132") (pin "K") (pinfunction "K_K") (pintype "passive"))
      (node (ref "D133") (pin "K") (pinfunction "K_K") (pintype "passive"))
      (node (ref "D134") (pin "K") (pinfunction "K_K") (pintype "passive"))
      (node (ref "D135") (pin "K") (pinfunction "K_K") (pintype "passive"))
      (node (ref "D136") (pin "K") (pinfunction "K_K") (pintype "passive"))
      (node (ref "D137") (pin "K") (pinfunction "K_K") (pintype "passive"))
      (node (ref "D138") (pin "K") (pinfunction "K_K") (pintype "passive"))
      (node (ref "D139") (pin "K") (pinfunction "K_K") (pintype "passive"))
      (node (ref "D140") (pin "K") (pinfunction "K_K") (pintype "passive"))
    )
    (net (code "34") (name "/MATRIX_K8") (class "Default")
      (node (ref "D141") (pin "K") (pinfunction "K_K") (pintype "passive"))
      (node (ref "D142") (pin "K") (pinfunction "K_K") (pintype "passive"))
      (node (ref "D143") (pin "K") (pinfunction "K_K") (pintype "passive"))
      (node (ref "D144") (pin "K") (pinfunction "K_K") (pintype "passive"))
      (node (ref "D145") (pin "K") (pinfunction "K_K") (pintype "passive"))
      (node (ref "D146") (pin "K") (pinfunction "K_K") (pintype "passive"))
      (node (ref "D147") (pin "K") (pinfunction "K_K") (pintype "passive"))
      (node (ref "D148") (pin "K") (pinfunction "K_K") (pintype "passive"))
      (node (ref "D149") (pin "K") (pinfunction "K_K") (pintype "passive"))
      (node (ref "D150") (pin "K") (pinfunction "K_K") (pintype "passive"))
      (node (ref "D151") (pin "K") (pinfunction "K_K") (pintype "passive"))
      (node (ref "D152") (pin "K") (pinfunction "K_K") (pintype "passive"))
      (node (ref "D153") (pin "K") (pinfunction "K_K") (pintype "passive"))
      (node (ref "D154") (pin "K") (pinfunction "K_K") (pintype "passive"))
      (node (ref "D155") (pin "K") (pinfunction "K_K") (pintype "passive"))
      (node (ref "D156") (pin "K") (pinfunction "K_K") (pintype "passive"))
      (node (ref "D157") (pin "K") (pinfunction "K_K") (pintype "passive"))
      (node (ref "D158") (pin "K") (pinfunction "K_K") (pintype "passive"))
      (node (ref "D159") (pin "K") (pinfunction "K_K") (pintype "passive"))
      (node (ref "D160") (pin "K") (pinfunction "K_K") (pintype "passive"))
      (node (ref "D161") (pin "K") (pinfunction "K_K") (pintype "passive"))
      (node (ref "D162") (pin "K") (pinfunction "K_K") (pintype "passive"))
      (node (ref "D163") (pin "K") (pinfunction "K_K") (pintype "passive"))
      (node (ref "D164") (pin "K") (pinfunction "K_K") (pintype "passive"))
      (node (ref "D165") (pin "K") (pinfunction "K_K") (pintype "passive"))
      (node (ref "D166") (pin "K") (pinfunction "K_K") (pintype "passive"))
    )
    (net (code "35") (name "/MATRIX_K9") (class "Default")
      (node (ref "D167") (pin "K") (pinfunction "K_K") (pintype "passive"))
      (node (ref "D168") (pin "K") (pinfunction "K_K") (pintype "passive"))
      (node (ref "D169") (pin "K") (pinfunction "K_K") (pintype "passive"))
      (node (ref "D170") (pin "K") (pinfunction "K_K") (pintype "passive"))
      (node (ref "D171") (pin "K") (pinfunction "K_K") (pintype "passive"))
      (node (ref "D172") (pin "K") (pinfunction "K_K") (pintype "passive"))
      (node (ref "D173") (pin "K") (pinfunction "K_K") (pintype "passive"))
      (node (ref "D174") (pin "K") (pinfunction "K_K") (pintype "passive"))
      (node (ref "D175") (pin "K") (pinfunction "K_K") (pintype "passive"))
      (node (ref "D176") (pin "K") (pinfunction "K_K") (pintype "passive"))
      (node (ref "D177") (pin "K") (pinfunction "K_K") (pintype "passive"))
      (node (ref "D178") (pin "K") (pinfunction "K_K") (pintype "passive"))
      (node (ref "D179") (pin "K") (pinfunction "K_K") (pintype "passive"))
      (node (ref "D180") (pin "K") (pinfunction "K_K") (pintype "passive"))
      (node (ref "D181") (pin "K") (pinfunction "K_K") (pintype "passive"))
      (node (ref "D182") (pin "K") (pinfunction "K_K") (pintype "passive"))
      (node (ref "D183") (pin "K") (pinfunction "K_K") (pintype "passive"))
      (node (ref "D184") (pin "K") (pinfunction "K_K") (pintype "passive"))
      (node (ref "D185") (pin "K") (pinfunction "K_K") (pintype "passive"))
      (node (ref "D186") (pin "K") (pinfunction "K_K") (pintype "passive"))
      (node (ref "D187") (pin "K") (pinfunction "K_K") (pintype "passive"))
      (node (ref "D188") (pin "K") (pinfunction "K_K") (pintype "passive"))
      (node (ref "D189") (pin "K") (pinfunction "K_K") (pintype "passive"))
      (node (ref "D190") (pin "K") (pinfunction "K_K") (pintype "passive"))
      (node (ref "D191") (pin "K") (pinfunction "K_K") (pintype "passive"))
      (node (ref "D192") (pin "K") (pinfunction "K_K") (pintype "passive"))
    )
    (net (code "36") (name "/MATRIX_K10") (class "Default")
      (node (ref "D193") (pin "K") (pinfunction "K_K") (pintype "passive"))
      (node (ref "D194") (pin "K") (pinfunction "K_K") (pintype "passive"))
      (node (ref "D195") (pin "K") (pinfunction "K_K") (pintype "passive"))
      (node (ref "D196") (pin "K") (pinfunction "K_K") (pintype "passive"))
      (node (ref "D197") (pin "K") (pinfunction "K_K") (pintype "passive"))
      (node (ref "D198") (pin "K") (pinfunction "K_K") (pintype "passive"))
      (node (ref "D199") (pin "K") (pinfunction "K_K") (pintype "passive"))
      (node (ref "D200") (pin "K") (pinfunction "K_K") (pintype "passive"))
      (node (ref "D201") (pin "K") (pinfunction "K_K") (pintype "passive"))
      (node (ref "D202") (pin "K") (pinfunction "K_K") (pintype "passive"))
      (node (ref "D203") (pin "K") (pinfunction "K_K") (pintype "passive"))
      (node (ref "D204") (pin "K") (pinfunction "K_K") (pintype "passive"))
      (node (ref "D205") (pin "K") (pinfunction "K_K") (pintype "passive"))
      (node (ref "D206") (pin "K") (pinfunction "K_K") (pintype "passive"))
      (node (ref "D207") (pin "K") (pinfunction "K_K") (pintype "passive"))
      (node (ref "D208") (pin "K") (pinfunction "K_K") (pintype "passive"))
      (node (ref "D209") (pin "K") (pinfunction "K_K") (pintype "passive"))
      (node (ref "D210") (pin "K") (pinfunction "K_K") (pintype "passive"))
      (node (ref "D211") (pin "K") (pinfunction "K_K") (pintype "passive"))
      (node (ref "D212") (pin "K") (pinfunction "K_K") (pintype "passive"))
      (node (ref "D213") (pin "K") (pinfunction "K_K") (pintype "passive"))
      (node (ref "D214") (pin "K") (pinfunction "K_K") (pintype "passive"))
      (node (ref "D215") (pin "K") (pinfunction "K_K") (pintype "passive"))
      (node (ref "D216") (pin "K") (pinfunction "K_K") (pintype "passive"))
      (node (ref "D217") (pin "K") (pinfunction "K_K") (pintype "passive"))
      (node (ref "D218") (pin "K") (pinfunction "K_K") (pintype "passive"))
    )
    (net (code "37") (name "/MATRIX_K11") (class "Default")
      (node (ref "D219") (pin "K") (pinfunction "K_K") (pintype "passive"))
      (node (ref "D220") (pin "K") (pinfunction "K_K") (pintype "passive"))
      (node (ref "D221") (pin "K") (pinfunction "K_K") (pintype "passive"))
      (node (ref "D222") (pin "K") (pinfunction "K_K") (pintype "passive"))
      (node (ref "D223") (pin "K") (pinfunction "K_K") (pintype "passive"))
      (node (ref "D224") (pin "K") (pinfunction "K_K") (pintype "passive"))
      (node (ref "D225") (pin "K") (pinfunction "K_K") (pintype "passive"))
      (node (ref "D226") (pin "K") (pinfunction "K_K") (pintype "passive"))
      (node (ref "D227") (pin "K") (pinfunction "K_K") (pintype "passive"))
      (node (ref "D228") (pin "K") (pinfunction "K_K") (pintype "passive"))
      (node (ref "D229") (pin "K") (pinfunction "K_K") (pintype "passive"))
      (node (ref "D230") (pin "K") (pinfunction "K_K") (pintype "passive"))
      (node (ref "D231") (pin "K") (pinfunction "K_K") (pintype "passive"))
      (node (ref "D232") (pin "K") (pinfunction "K_K") (pintype "passive"))
      (node (ref "D233") (pin "K") (pinfunction "K_K") (pintype "passive"))
      (node (ref "D234") (pin "K") (pinfunction "K_K") (pintype "passive"))
      (node (ref "D235") (pin "K") (pinfunction "K_K") (pintype "passive"))
      (node (ref "D236") (pin "K") (pinfunction "K_K") (pintype "passive"))
      (node (ref "D237") (pin "K") (pinfunction "K_K") (pintype "passive"))
      (node (ref "D238") (pin "K") (pinfunction "K_K") (pintype "passive"))
      (node (ref "D239") (pin "K") (pinfunction "K_K") (pintype "passive"))
      (node (ref "D240") (pin "K") (pinfunction "K_K") (pintype "passive"))
      (node (ref "D241") (pin "K") (pinfunction "K_K") (pintype "passive"))
      (node (ref "D242") (pin "K") (pinfunction "K_K") (pintype "passive"))
    )
    (net (code "38") (name "/MATRIX_K12") (class "Default")
      (node (ref "D243") (pin "K") (pinfunction "K_K") (pintype "passive"))
      (node (ref "D244") (pin "K") (pinfunction "K_K") (pintype "passive"))
      (node (ref "D245") (pin "K") (pinfunction "K_K") (pintype "passive"))
      (node (ref "D246") (pin "K") (pinfunction "K_K") (pintype "passive"))
      (node (ref "D247") (pin "K") (pinfunction "K_K") (pintype "passive"))
      (node (ref "D248") (pin "K") (pinfunction "K_K") (pintype "passive"))
      (node (ref "D249") (pin "K") (pinfunction "K_K") (pintype "passive"))
      (node (ref "D250") (pin "K") (pinfunction "K_K") (pintype "passive"))
      (node (ref "D251") (pin "K") (pinfunction "K_K") (pintype "passive"))
      (node (ref "D252") (pin "K") (pinfunction "K_K") (pintype "passive"))
      (node (ref "D253") (pin "K") (pinfunction "K_K") (pintype "passive"))
      (node (ref "D254") (pin "K") (pinfunction "K_K") (pintype "passive"))
      (node (ref "D255") (pin "K") (pinfunction "K_K") (pintype "passive"))
      (node (ref "D256") (pin "K") (pinfunction "K_K") (pintype "passive"))
      (node (ref "D257") (pin "K") (pinfunction "K_K") (pintype "passive"))
      (node (ref "D258") (pin "K") (pinfunction "K_K") (pintype "passive"))
      (node (ref "D259") (pin "K") (pinfunction "K_K") (pintype "passive"))
      (node (ref "D260") (pin "K") (pinfunction "K_K") (pintype "passive"))
      (node (ref "D261") (pin "K") (pinfunction "K_K") (pintype "passive"))
      (node (ref "D262") (pin "K") (pinfunction "K_K") (pintype "passive"))
      (node (ref "D263") (pin "K") (pinfunction "K_K") (pintype "passive"))
      (node (ref "D264") (pin "K") (pinfunction "K_K") (pintype "passive"))
      (node (ref "D265") (pin "K") (pinfunction "K_K") (pintype "passive"))
      (node (ref "D266") (pin "K") (pinfunction "K_K") (pintype "passive"))
    )
    (net (code "39") (name "/MATRIX_K13") (class "Default")
      (node (ref "D267") (pin "K") (pinfunction "K_K") (pintype "passive"))
      (node (ref "D268") (pin "K") (pinfunction "K_K") (pintype "passive"))
      (node (ref "D269") (pin "K") (pinfunction "K_K") (pintype "passive"))
      (node (ref "D270") (pin "K") (pinfunction "K_K") (pintype "passive"))
      (node (ref "D271") (pin "K") (pinfunction "K_K") (pintype "passive"))
      (node (ref "D272") (pin "K") (pinfunction "K_K") (pintype "passive"))
      (node (ref "D273") (pin "K") (pinfunction "K_K") (pintype "passive"))
      (node (ref "D274") (pin "K") (pinfunction "K_K") (pintype "passive"))
      (node (ref "D275") (pin "K") (pinfunction "K_K") (pintype "passive"))
      (node (ref "D276") (pin "K") (pinfunction "K_K") (pintype "passive"))
      (node (ref "D277") (pin "K") (pinfunction "K_K") (pintype "passive"))
      (node (ref "D278") (pin "K") (pinfunction "K_K") (pintype "passive"))
      (node (ref "D279") (pin "K") (pinfunction "K_K") (pintype "passive"))
      (node (ref "D280") (pin "K") (pinfunction "K_K") (pintype "passive"))
      (node (ref "D281") (pin "K") (pinfunction "K_K") (pintype "passive"))
      (node (ref "D282") (pin "K") (pinfunction "K_K") (pintype "passive"))
      (node (ref "D283") (pin "K") (pinfunction "K_K") (pintype "passive"))
      (node (ref "D284") (pin "K") (pinfunction "K_K") (pintype "passive"))
      (node (ref "D285") (pin "K") (pinfunction "K_K") (pintype "passive"))
      (node (ref "D286") (pin "K") (pinfunction "K_K") (pintype "passive"))
      (node (ref "D287") (pin "K") (pinfunction "K_K") (pintype "passive"))
      (node (ref "D288") (pin "K") (pinfunction "K_K") (pintype "passive"))
    )
    (net (code "40") (name "/MATRIX_K14") (class "Default")
      (node (ref "D289") (pin "K") (pinfunction "K_K") (pintype "passive"))
      (node (ref "D290") (pin "K") (pinfunction "K_K") (pintype "passive"))
      (node (ref "D291") (pin "K") (pinfunction "K_K") (pintype "passive"))
      (node (ref "D292") (pin "K") (pinfunction "K_K") (pintype "passive"))
      (node (ref "D293") (pin "K") (pinfunction "K_K") (pintype "passive"))
      (node (ref "D294") (pin "K") (pinfunction "K_K") (pintype "passive"))
      (node (ref "D295") (pin "K") (pinfunction "K_K") (pintype "passive"))
      (node (ref "D296") (pin "K") (pinfunction "K_K") (pintype "passive"))
      (node (ref "D297") (pin "K") (pinfunction "K_K") (pintype "passive"))
      (node (ref "D298") (pin "K") (pinfunction "K_K") (pintype "passive"))
      (node (ref "D299") (pin "K") (pinfunction "K_K") (pintype "passive"))
      (node (ref "D300") (pin "K") (pinfunction "K_K") (pintype "passive"))
      (node (ref "D301") (pin "K") (pinfunction "K_K") (pintype "passive"))
      (node (ref "D302") (pin "K") (pinfunction "K_K") (pintype "passive"))
      (node (ref "D303") (pin "K") (pinfunction "K_K") (pintype "passive"))
      (node (ref "D304") (pin "K") (pinfunction "K_K") (pintype "passive"))
      (node (ref "D305") (pin "K") (pinfunction "K_K") (pintype "passive"))
      (node (ref "D306") (pin "K") (pinfunction "K_K") (pintype "passive"))
      (node (ref "D307") (pin "K") (pinfunction "K_K") (pintype "passive"))
      (node (ref "D308") (pin "K") (pinfunction "K_K") (pintype "passive"))
    )
    (net (code "41") (name "/MATRIX_K15") (class "Default")
      (node (ref "D309") (pin "K") (pinfunction "K_K") (pintype "passive"))
      (node (ref "D310") (pin "K") (pinfunction "K_K") (pintype "passive"))
      (node (ref "D311") (pin "K") (pinfunction "K_K") (pintype "passive"))
      (node (ref "D312") (pin "K") (pinfunction "K_K") (pintype "passive"))
      (node (ref "D313") (pin "K") (pinfunction "K_K") (pintype "passive"))
      (node (ref "D314") (pin "K") (pinfunction "K_K") (pintype "passive"))
      (node (ref "D315") (pin "K") (pinfunction "K_K") (pintype "passive"))
      (node (ref "D316") (pin "K") (pinfunction "K_K") (pintype "passive"))
      (node (ref "D317") (pin "K") (pinfunction "K_K") (pintype "passive"))
      (node (ref "D318") (pin "K") (pinfunction "K_K") (pintype "passive"))
      (node (ref "D319") (pin "K") (pinfunction "K_K") (pintype "passive"))
      (node (ref "D320") (pin "K") (pinfunction "K_K") (pintype "passive"))
      (node (ref "D321") (pin "K") (pinfunction "K_K") (pintype "passive"))
      (node (ref "D322") (pin "K") (pinfunction "K_K") (pintype "passive"))
      (node (ref "D323") (pin "K") (pinfunction "K_K") (pintype "passive"))
      (node (ref "D324") (pin "K") (pinfunction "K_K") (pintype "passive"))
      (node (ref "D325") (pin "K") (pinfunction "K_K") (pintype "passive"))
      (node (ref "D326") (pin "K") (pinfunction "K_K") (pintype "passive"))
    )
    (net (code "42") (name "/MATRIX_K16") (class "Default")
      (node (ref "D327") (pin "K") (pinfunction "K_K") (pintype "passive"))
      (node (ref "D328") (pin "K") (pinfunction "K_K") (pintype "passive"))
      (node (ref "D329") (pin "K") (pinfunction "K_K") (pintype "passive"))
      (node (ref "D330") (pin "K") (pinfunction "K_K") (pintype "passive"))
      (node (ref "D331") (pin "K") (pinfunction "K_K") (pintype "passive"))
      (node (ref "D332") (pin "K") (pinfunction "K_K") (pintype "passive"))
      (node (ref "D333") (pin "K") (pinfunction "K_K") (pintype "passive"))
      (node (ref "D334") (pin "K") (pinfunction "K_K") (pintype "passive"))
      (node (ref "D335") (pin "K") (pinfunction "K_K") (pintype "passive"))
      (node (ref "D336") (pin "K") (pinfunction "K_K") (pintype "passive"))
      (node (ref "D337") (pin "K") (pinfunction "K_K") (pintype "passive"))
      (node (ref "D338") (pin "K") (pinfunction "K_K") (pintype "passive"))
      (node (ref "D339") (pin "K") (pinfunction "K_K") (pintype "passive"))
      (node (ref "D340") (pin "K") (pinfunction "K_K") (pintype "passive"))
      (node (ref "D341") (pin "K") (pinfunction "K_K") (pintype "passive"))
      (node (ref "D342") (pin "K") (pinfunction "K_K") (pintype "passive"))
    )
    (net (code "43") (name "/MATRIX_K17") (class "Default")
      (node (ref "D343") (pin "K") (pinfunction "K_K") (pintype "passive"))
      (node (ref "D344") (pin "K") (pinfunction "K_K") (pintype "passive"))
      (node (ref "D345") (pin "K") (pinfunction "K_K") (pintype "passive"))
      (node (ref "D346") (pin "K") (pinfunction "K_K") (pintype "passive"))
      (node (ref "D347") (pin "K") (pinfunction "K_K") (pintype "passive"))
      (node (ref "D348") (pin "K") (pinfunction "K_K") (pintype "passive"))
      (node (ref "D349") (pin "K") (pinfunction "K_K") (pintype "passive"))
      (node (ref "D350") (pin "K") (pinfunction "K_K") (pintype "passive"))
      (node (ref "D351") (pin "K") (pinfunction "K_K") (pintype "passive"))
      (node (ref "D352") (pin "K") (pinfunction "K_K") (pintype "passive"))
      (node (ref "D353") (pin "K") (pinfunction "K_K") (pintype "passive"))
      (node (ref "D354") (pin "K") (pinfunction "K_K") (pintype "passive"))
      (node (ref "D355") (pin "K") (pinfunction "K_K") (pintype "passive"))
      (node (ref "D356") (pin "K") (pinfunction "K_K") (pintype "passive"))
    )
    (net (code "44") (name "/MATRIX_K18") (class "Default")
      (node (ref "D357") (pin "K") (pinfunction "K_K") (pintype "passive"))
      (node (ref "D358") (pin "K") (pinfunction "K_K") (pintype "passive"))
      (node (ref "D359") (pin "K") (pinfunction "K_K") (pintype "passive"))
      (node (ref "D360") (pin "K") (pinfunction "K_K") (pintype "passive"))
      (node (ref "D361") (pin "K") (pinfunction "K_K") (pintype "passive"))
      (node (ref "D362") (pin "K") (pinfunction "K_K") (pintype "passive"))
      (node (ref "D363") (pin "K") (pinfunction "K_K") (pintype "passive"))
      (node (ref "D364") (pin "K") (pinfunction "K_K") (pintype "passive"))
      (node (ref "D365") (pin "K") (pinfunction "K_K") (pintype "passive"))
      (node (ref "D366") (pin "K") (pinfunction "K_K") (pintype "passive"))
      (node (ref "D367") (pin "K") (pinfunction "K_K") (pintype "passive"))
      (node (ref "D368") (pin "K") (pinfunction "K_K") (pintype "passive"))
    )
    (net (code "45") (name "/MATRIX_K19") (class "Default")
      (node (ref "D369") (pin "K") (pinfunction "K_K") (pintype "passive"))
      (node (ref "D370") (pin "K") (pinfunction "K_K") (pintype "passive"))
      (node (ref "D371") (pin "K") (pinfunction "K_K") (pintype "passive"))
      (node (ref "D372") (pin "K") (pinfunction "K_K") (pintype "passive"))
      (node (ref "D373") (pin "K") (pinfunction "K_K") (pintype "passive"))
      (node (ref "D374") (pin "K") (pinfunction "K_K") (pintype "passive"))
      (node (ref "D375") (pin "K") (pinfunction "K_K") (pintype "passive"))
      (node (ref "D376") (pin "K") (pinfunction "K_K") (pintype "passive"))
      (node (ref "D377") (pin "K") (pinfunction "K_K") (pintype "passive"))
      (node (ref "D378") (pin "K") (pinfunction "K_K") (pintype "passive"))
    )
    (net (code "46") (name "/MATRIX_K20") (class "Default")
      (node (ref "D379") (pin "K") (pinfunction "K_K") (pintype "passive"))
      (node (ref "D380") (pin "K") (pinfunction "K_K") (pintype "passive"))
      (node (ref "D381") (pin "K") (pinfunction "K_K") (pintype "passive"))
      (node (ref "D382") (pin "K") (pinfunction "K_K") (pintype "passive"))
      (node (ref "D383") (pin "K") (pinfunction "K_K") (pintype "passive"))
      (node (ref "D384") (pin "K") (pinfunction "K_K") (pintype "passive"))
      (node (ref "D385") (pin "K") (pinfunction "K_K") (pintype "passive"))
      (node (ref "D386") (pin "K") (pinfunction "K_K") (pintype "passive"))
    )
    (net (code "47") (name "/MATRIX_K21") (class "Default")
      (node (ref "D387") (pin "K") (pinfunction "K_K") (pintype "passive"))
      (node (ref "D388") (pin "K") (pinfunction "K_K") (pintype "passive"))
      (node (ref "D389") (pin "K") (pinfunction "K_K") (pintype "passive"))
      (node (ref "D390") (pin "K") (pinfunction "K_K") (pintype "passive"))
      (node (ref "D391") (pin "K") (pinfunction "K_K") (pintype "passive"))
      (node (ref "D392") (pin "K") (pinfunction "K_K") (pintype "passive"))
    )
    (net (code "48") (name "/MATRIX_K22") (class "Default")
      (node (ref "D393") (pin "K") (pinfunction "K_K") (pintype "passive"))
      (node (ref "D394") (pin "K") (pinfunction "K_K") (pintype "passive"))
      (node (ref "D395") (pin "K") (pinfunction "K_K") (pintype "passive"))
      (node (ref "D396") (pin "K") (pinfunction "K_K") (pintype "passive"))
    )
    (net (code "49") (name "/MATRIX_K23") (class "Default")
      (node (ref "D397") (pin "K") (pinfunction "K_K") (pintype "passive"))
      (node (ref "D398") (pin "K") (pinfunction "K_K") (pintype "passive"))
    )
  )
)
